# Ice-LogicBench.net
KiCad netlist of a schematic drawn in EAGLE
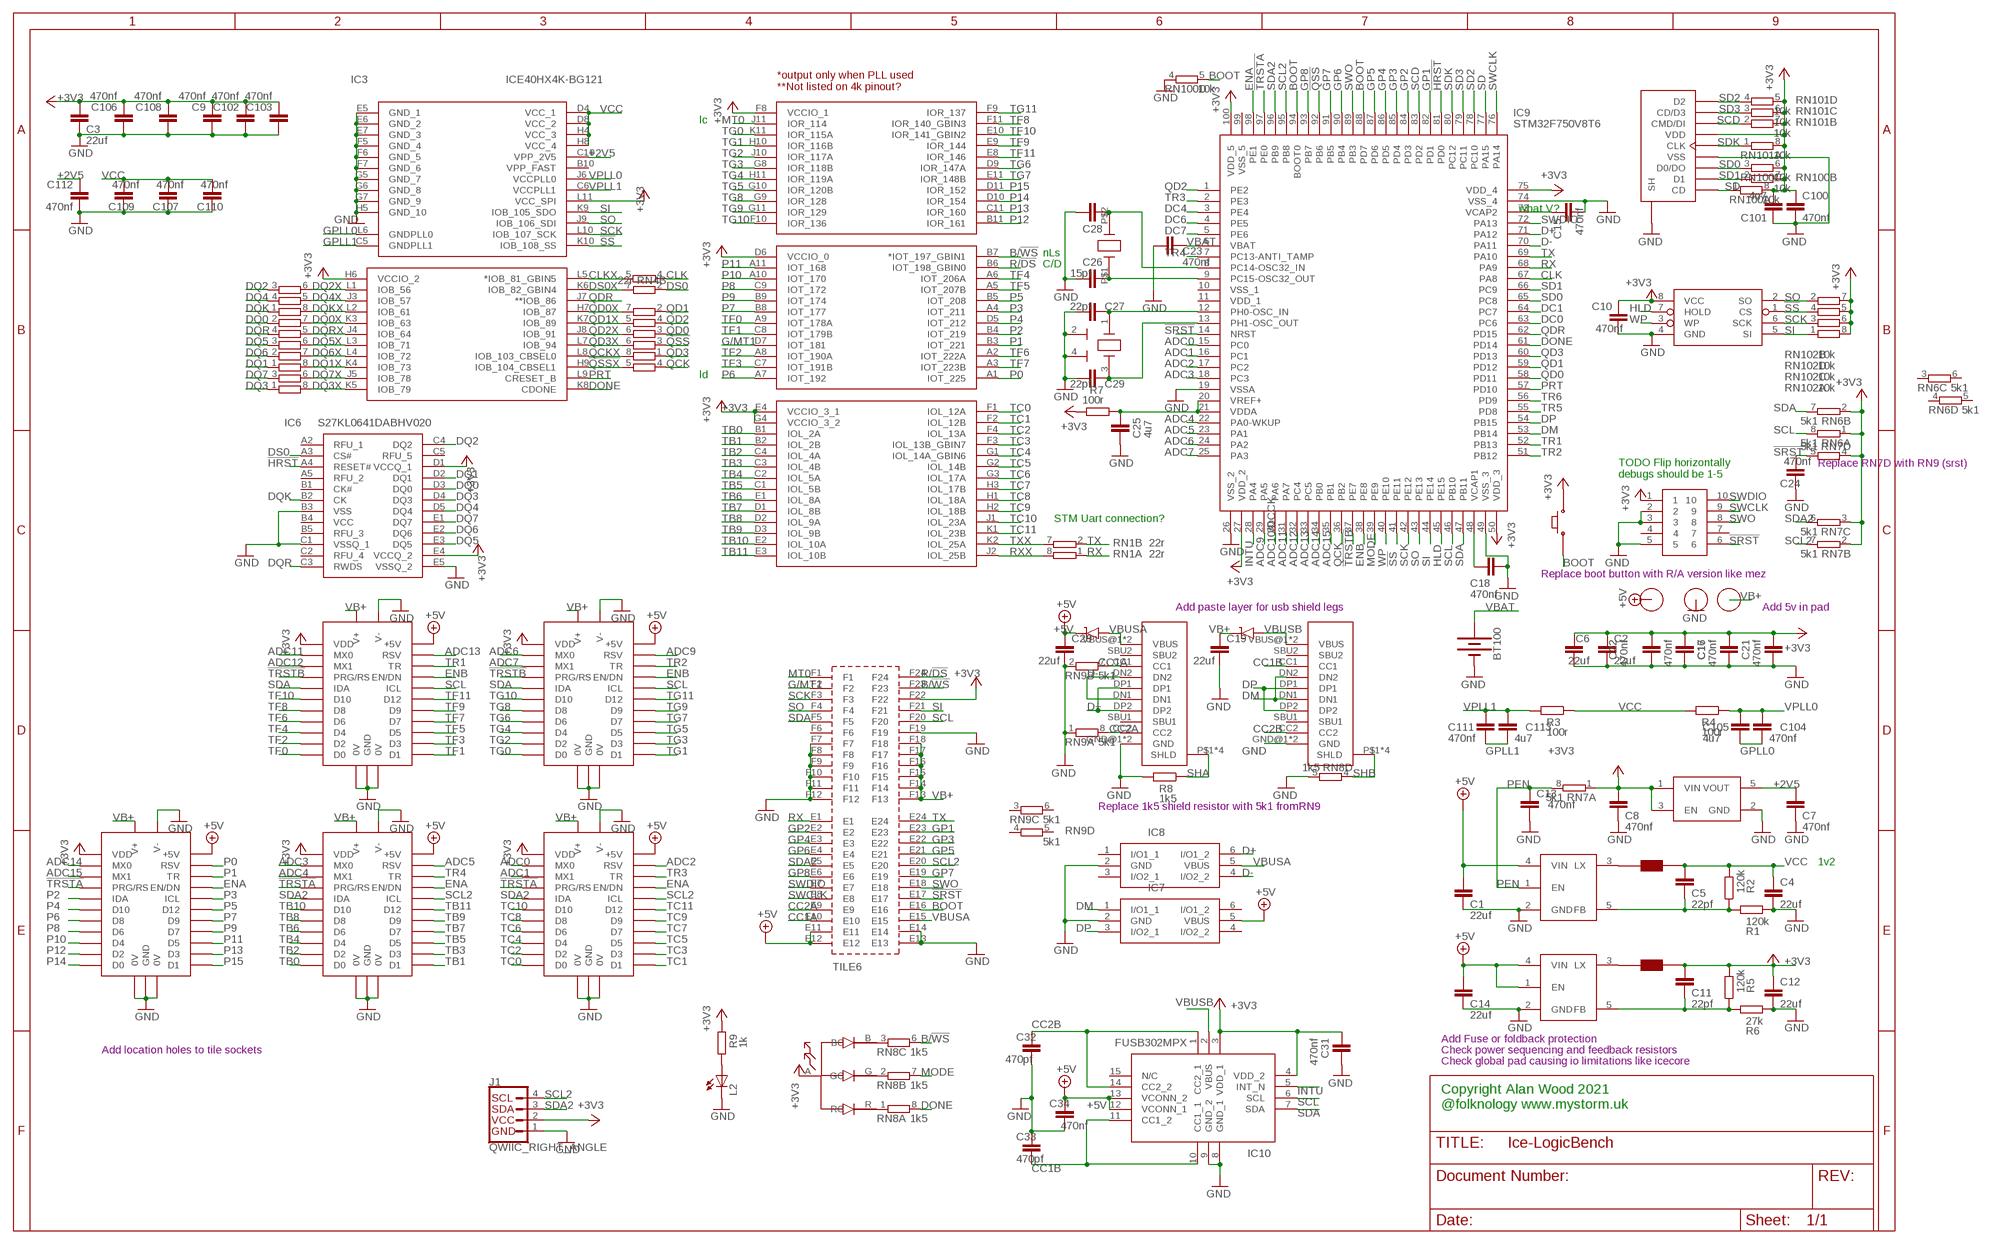
[diagram p0: schematic, sheet 1]

(export (version "E")
  (design (tool "Eeschema 10.0.6"))
  (components
    (comp (ref "B1")
      (value "PUSH_BUTTON")
      (footprint "eagle-import:3X4MM_BUTTON")
      (libsource (lib "eagle-import") (part "PUSH_BUTTON"))
    )
    (comp (ref "BT100")
      (value "BATTERY-20MM_SMD")
      (footprint "eagle-import:BATTCON_20MM")
      (libsource (lib "eagle-import") (part "BATTERY-20MM_SMD"))
    )
    (comp (ref "C1")
      (value "22uf")
      (footprint "eagle-import:C0603")
      (libsource (lib "eagle-import") (part "C-EUC0603"))
    )
    (comp (ref "C2")
      (value "22uf")
      (footprint "eagle-import:C0603")
      (libsource (lib "eagle-import") (part "C-EUC0603"))
    )
    (comp (ref "C3")
      (value "22uf")
      (footprint "eagle-import:C0603")
      (libsource (lib "eagle-import") (part "C-EUC0603"))
    )
    (comp (ref "C4")
      (value "22uf")
      (footprint "eagle-import:C0603")
      (libsource (lib "eagle-import") (part "C-EUC0603"))
    )
    (comp (ref "C5")
      (value "22pf")
      (footprint "eagle-import:C0402")
      (libsource (lib "eagle-import") (part "C-EUC0402"))
    )
    (comp (ref "C6")
      (value "22uf")
      (footprint "eagle-import:C0603")
      (libsource (lib "eagle-import") (part "C-EUC0603"))
    )
    (comp (ref "C7")
      (value "470nf")
      (footprint "eagle-import:C0402")
      (libsource (lib "eagle-import") (part "C-EUC0402"))
    )
    (comp (ref "C8")
      (value "470nf")
      (footprint "eagle-import:C0402")
      (libsource (lib "eagle-import") (part "C-EUC0402"))
    )
    (comp (ref "C9")
      (value "470nf")
      (footprint "eagle-import:C0402")
      (libsource (lib "eagle-import") (part "C-EUC0402"))
    )
    (comp (ref "C10")
      (value "470nf")
      (footprint "eagle-import:C0402")
      (libsource (lib "eagle-import") (part "C-EUC0402"))
    )
    (comp (ref "C11")
      (value "22pf")
      (footprint "eagle-import:C0402")
      (libsource (lib "eagle-import") (part "C-EUC0402"))
    )
    (comp (ref "C12")
      (value "22uf")
      (footprint "eagle-import:C0603")
      (libsource (lib "eagle-import") (part "C-EUC0603"))
    )
    (comp (ref "C13")
      (value "470nf")
      (footprint "eagle-import:C0402")
      (libsource (lib "eagle-import") (part "C-EUC0402"))
    )
    (comp (ref "C14")
      (value "22uf")
      (footprint "eagle-import:C0603")
      (libsource (lib "eagle-import") (part "C-EUC0603"))
    )
    (comp (ref "C15")
      (value "470nf")
      (footprint "eagle-import:C0402")
      (libsource (lib "eagle-import") (part "C-EUC0402"))
    )
    (comp (ref "C16")
      (value "470nf")
      (footprint "eagle-import:C0402")
      (libsource (lib "eagle-import") (part "C-EUC0402"))
    )
    (comp (ref "C17")
      (value "470nf")
      (footprint "eagle-import:C0402")
      (libsource (lib "eagle-import") (part "C-EUC0402"))
    )
    (comp (ref "C18")
      (value "470nf")
      (footprint "eagle-import:C0402")
      (libsource (lib "eagle-import") (part "C-EUC0402"))
    )
    (comp (ref "C19")
      (value "22uf")
      (footprint "eagle-import:C0603")
      (libsource (lib "eagle-import") (part "C-EUC0603"))
    )
    (comp (ref "C20")
      (value "22uf")
      (footprint "eagle-import:C0603")
      (libsource (lib "eagle-import") (part "C-EUC0603"))
    )
    (comp (ref "C21")
      (value "470nf")
      (footprint "eagle-import:C0402")
      (libsource (lib "eagle-import") (part "C-EUC0402"))
    )
    (comp (ref "C22")
      (value "470nf")
      (footprint "eagle-import:C0402")
      (libsource (lib "eagle-import") (part "C-EUC0402"))
    )
    (comp (ref "C23")
      (value "470nf")
      (footprint "eagle-import:C0402")
      (libsource (lib "eagle-import") (part "C-EUC0402"))
    )
    (comp (ref "C24")
      (value "470nf")
      (footprint "eagle-import:C0402")
      (libsource (lib "eagle-import") (part "C-EUC0402"))
    )
    (comp (ref "C25")
      (value "4u7")
      (footprint "eagle-import:C0402")
      (libsource (lib "eagle-import") (part "C-EUC0402"))
    )
    (comp (ref "C26")
      (value "15pf")
      (footprint "eagle-import:C0402")
      (libsource (lib "eagle-import") (part "C-EUC0402"))
    )
    (comp (ref "C27")
      (value "22pf")
      (footprint "eagle-import:C0402")
      (libsource (lib "eagle-import") (part "C-EUC0402"))
    )
    (comp (ref "C28")
      (value "15pf")
      (footprint "eagle-import:C0402")
      (libsource (lib "eagle-import") (part "C-EUC0402"))
    )
    (comp (ref "C29")
      (value "22pf")
      (footprint "eagle-import:C0402")
      (libsource (lib "eagle-import") (part "C-EUC0402"))
    )
    (comp (ref "C31")
      (value "470nf")
      (footprint "eagle-import:C0402")
      (libsource (lib "eagle-import") (part "C-EUC0402"))
    )
    (comp (ref "C32")
      (value "470pf")
      (footprint "eagle-import:C0402")
      (libsource (lib "eagle-import") (part "C-EUC0402"))
    )
    (comp (ref "C33")
      (value "470pf")
      (footprint "eagle-import:C0402")
      (libsource (lib "eagle-import") (part "C-EUC0402"))
    )
    (comp (ref "C34")
      (value "470nf")
      (footprint "eagle-import:C0402")
      (libsource (lib "eagle-import") (part "C-EUC0402"))
    )
    (comp (ref "C100")
      (value "470nf")
      (footprint "eagle-import:C0402")
      (libsource (lib "eagle-import") (part "C-EUC0402"))
    )
    (comp (ref "C101")
      (value "4u7")
      (footprint "eagle-import:C0402")
      (libsource (lib "eagle-import") (part "C-EUC0402"))
    )
    (comp (ref "C102")
      (value "470nf")
      (footprint "eagle-import:C0402")
      (libsource (lib "eagle-import") (part "C-EUC0402"))
    )
    (comp (ref "C103")
      (value "470nf")
      (footprint "eagle-import:C0402")
      (libsource (lib "eagle-import") (part "C-EUC0402"))
    )
    (comp (ref "C104")
      (value "470nf")
      (footprint "eagle-import:C0402")
      (libsource (lib "eagle-import") (part "C-EUC0402"))
    )
    (comp (ref "C105")
      (value "4u7")
      (footprint "eagle-import:C0402")
      (libsource (lib "eagle-import") (part "C-EUC0402"))
    )
    (comp (ref "C106")
      (value "470nf")
      (footprint "eagle-import:C0402")
      (libsource (lib "eagle-import") (part "C-EUC0402"))
    )
    (comp (ref "C107")
      (value "470nf")
      (footprint "eagle-import:C0402")
      (libsource (lib "eagle-import") (part "C-EUC0402"))
    )
    (comp (ref "C108")
      (value "470nf")
      (footprint "eagle-import:C0402")
      (libsource (lib "eagle-import") (part "C-EUC0402"))
    )
    (comp (ref "C109")
      (value "470nf")
      (footprint "eagle-import:C0402")
      (libsource (lib "eagle-import") (part "C-EUC0402"))
    )
    (comp (ref "C110")
      (value "470nf")
      (footprint "eagle-import:C0402")
      (libsource (lib "eagle-import") (part "C-EUC0402"))
    )
    (comp (ref "C111")
      (value "470nf")
      (footprint "eagle-import:C0402")
      (libsource (lib "eagle-import") (part "C-EUC0402"))
    )
    (comp (ref "C112")
      (value "470nf")
      (footprint "eagle-import:C0402")
      (libsource (lib "eagle-import") (part "C-EUC0402"))
    )
    (comp (ref "C113")
      (value "4u7")
      (footprint "eagle-import:C0402")
      (libsource (lib "eagle-import") (part "C-EUC0402"))
    )
    (comp (ref "CN1")
      (value "USB-C-16")
      (footprint "eagle-import:USB-C")
      (libsource (lib "eagle-import") (part "USB-C-16"))
    )
    (comp (ref "CN2")
      (value "USB-C-16")
      (footprint "eagle-import:USB-C")
      (libsource (lib "eagle-import") (part "USB-C-16"))
    )
    (comp (ref "CN3")
      (value "2X5-HEADER")
      (footprint "eagle-import:1.27-2X5-HEADER")
      (libsource (lib "eagle-import") (part "2X5-HEADER"))
    )
    (comp (ref "H1")
      (value "HOLE2.5MM-LARGE")
      (footprint "eagle-import:2M5-LARGE")
      (libsource (lib "eagle-import") (part "HOLE2.5MM-LARGE"))
    )
    (comp (ref "H3")
      (value "HOLE2.5MM-LARGE")
      (footprint "eagle-import:2M5-LARGE")
      (libsource (lib "eagle-import") (part "HOLE2.5MM-LARGE"))
    )
    (comp (ref "H4")
      (value "HOLE2.5MM-LARGE")
      (footprint "eagle-import:2M5-LARGE")
      (libsource (lib "eagle-import") (part "HOLE2.5MM-LARGE"))
    )
    (comp (ref "I1")
      (value "NRS4018")
      (footprint "eagle-import:NRC4018")
      (libsource (lib "eagle-import") (part "NRS4018"))
    )
    (comp (ref "I2")
      (value "NRS4018")
      (footprint "eagle-import:NRC4018")
      (libsource (lib "eagle-import") (part "NRS4018"))
    )
    (comp (ref "IC1")
      (value "AP3429/A")
      (footprint "eagle-import:TSOP-5_SOT23-5")
      (libsource (lib "eagle-import") (part "AP3429/A"))
    )
    (comp (ref "IC2")
      (value "NCP114")
      (footprint "eagle-import:TSOP-5_SOT23-5")
      (libsource (lib "eagle-import") (part "NCP114"))
    )
    (comp (ref "IC3")
      (value "ICE40HX4K-BG121")
      (footprint "eagle-import:BGA121C80P11X11_900X900X110")
      (fields (field (name "MOUSER_PART_NUMBER") "842-ICE40HX4K-BG121"))
      (libsource (lib "eagle-import") (part "ICE40HX4K-BG121"))
    )
    (comp (ref "IC4")
      (value "AT25SDF041A")
      (footprint "eagle-import:SOIC-8-NARROW")
      (libsource (lib "eagle-import") (part "AT25SDF041A"))
    )
    (comp (ref "IC5")
      (value "AP3429/A")
      (footprint "eagle-import:TSOP-5_SOT23-5")
      (libsource (lib "eagle-import") (part "AP3429/A"))
    )
    (comp (ref "IC6")
      (value "S27KL0641DABHV020")
      (footprint "eagle-import:BGA24C100P5X5_600X800X100")
      (fields (field (name "MOUSER_PART_NUMBER") "727-S27KL0641DABHV02"))
      (libsource (lib "eagle-import") (part "S27KL0641DABHV020"))
    )
    (comp (ref "IC7")
      (value "USBLC6-2SC6")
      (footprint "eagle-import:SOT95P280X145-6N")
      (fields (field (name "MOUSER_PART_NUMBER") "511-USBLC6-2SC6"))
      (libsource (lib "eagle-import") (part "USBLC6-2SC6"))
    )
    (comp (ref "IC8")
      (value "USBLC6-2SC6")
      (footprint "eagle-import:SOT95P280X145-6N")
      (fields (field (name "MOUSER_PART_NUMBER") "511-USBLC6-2SC6"))
      (libsource (lib "eagle-import") (part "USBLC6-2SC6"))
    )
    (comp (ref "IC9")
      (value "STM32F750V8T6")
      (footprint "eagle-import:QFP50P1600X1600X160-100N")
      (fields (field (name "MOUSER_PART_NUMBER") "511-STM32F750V8T6"))
      (libsource (lib "eagle-import") (part "STM32F750V8T6"))
    )
    (comp (ref "IC10")
      (value "FUSB302MPX")
      (footprint "eagle-import:QFN50P250X250X80-15N")
      (fields (field (name "MOUSER_PART_NUMBER") "512-FUSB302MPX"))
      (libsource (lib "eagle-import") (part "FUSB302MPX"))
    )
    (comp (ref "J1")
      (value "QWIIC_RIGHT_ANGLE")
      (footprint "eagle-import:JST04_1MM_RA")
      (libsource (lib "eagle-import") (part "QWIIC_CONNECTORJS-1MM"))
    )
    (comp (ref "L1")
      (value "RGB_LED")
      (footprint "eagle-import:RGB_LED_IMM")
      (libsource (lib "eagle-import") (part "RGB_LED"))
    )
    (comp (ref "L2")
      (value "LEDCHIPLED_1206")
      (footprint "eagle-import:CHIPLED_1206")
      (libsource (lib "eagle-import") (part "LEDCHIPLED_1206"))
    )
    (comp (ref "R1")
      (value "120k")
      (footprint "eagle-import:R0402")
      (libsource (lib "eagle-import") (part "R-EU_R0402"))
    )
    (comp (ref "R2")
      (value "120k")
      (footprint "eagle-import:R0402")
      (libsource (lib "eagle-import") (part "R-EU_R0402"))
    )
    (comp (ref "R3")
      (value "100r")
      (footprint "eagle-import:R0402")
      (libsource (lib "eagle-import") (part "R-EU_R0402"))
    )
    (comp (ref "R4")
      (value "100r")
      (footprint "eagle-import:R0402")
      (libsource (lib "eagle-import") (part "R-EU_R0402"))
    )
    (comp (ref "R5")
      (value "120k")
      (footprint "eagle-import:R0402")
      (libsource (lib "eagle-import") (part "R-EU_R0402"))
    )
    (comp (ref "R6")
      (value "27k")
      (footprint "eagle-import:R0402")
      (libsource (lib "eagle-import") (part "R-EU_R0402"))
    )
    (comp (ref "R7")
      (value "100r")
      (footprint "eagle-import:R0402")
      (libsource (lib "eagle-import") (part "R-EU_R0402"))
    )
    (comp (ref "R8")
      (value "1k5")
      (footprint "eagle-import:R0402")
      (libsource (lib "eagle-import") (part "R-EU_R0402"))
    )
    (comp (ref "R9")
      (value "1k")
      (footprint "eagle-import:R0402")
      (libsource (lib "eagle-import") (part "R-EU_R0402"))
    )
    (comp (ref "RN1")
      (value "22r")
      (footprint "eagle-import:EXB38V")
      (libsource (lib "eagle-import") (part "4R-NEXB38V"))
    )
    (comp (ref "RN2")
      (value "22r")
      (footprint "eagle-import:EXB38V")
      (libsource (lib "eagle-import") (part "4R-NEXB38V"))
    )
    (comp (ref "RN3")
      (value "22r")
      (footprint "eagle-import:EXB38V")
      (libsource (lib "eagle-import") (part "4R-NEXB38V"))
    )
    (comp (ref "RN4")
      (value "22r")
      (footprint "eagle-import:EXB38V")
      (libsource (lib "eagle-import") (part "4R-NEXB38V"))
    )
    (comp (ref "RN5")
      (value "22r")
      (footprint "eagle-import:EXB38V")
      (libsource (lib "eagle-import") (part "4R-NEXB38V"))
    )
    (comp (ref "RN6")
      (value "5k1")
      (footprint "eagle-import:EXB38V")
      (libsource (lib "eagle-import") (part "4R-NEXB38V"))
    )
    (comp (ref "RN7")
      (value "5k1")
      (footprint "eagle-import:EXB38V")
      (libsource (lib "eagle-import") (part "4R-NEXB38V"))
    )
    (comp (ref "RN8")
      (value "1k5")
      (footprint "eagle-import:EXB38V")
      (libsource (lib "eagle-import") (part "4R-NEXB38V"))
    )
    (comp (ref "RN9")
      (value "5k1")
      (footprint "eagle-import:EXB38V")
      (libsource (lib "eagle-import") (part "4R-NEXB38V"))
    )
    (comp (ref "RN100")
      (value "10k")
      (footprint "eagle-import:EXB38V")
      (libsource (lib "eagle-import") (part "4R-NEXB38V"))
    )
    (comp (ref "RN101")
      (value "10k")
      (footprint "eagle-import:EXB38V")
      (libsource (lib "eagle-import") (part "4R-NEXB38V"))
    )
    (comp (ref "RN102")
      (value "10k")
      (footprint "eagle-import:EXB38V")
      (libsource (lib "eagle-import") (part "4R-NEXB38V"))
    )
    (comp (ref "SD100")
      (value "TF-15X15")
      (footprint "eagle-import:SDCARD")
      (libsource (lib "eagle-import") (part "TF-15X15"))
    )
    (comp (ref "TILE1")
      (value "UTILE_LPCARRIER_SMD_MALE_1.27")
      (footprint "eagle-import:UTILE_LP")
      (libsource (lib "eagle-import") (part "UTILE_LPCARRIER_SMD_MALE_1.27"))
    )
    (comp (ref "TILE2")
      (value "UTILE_LPCARRIER_SMD_MALE_1.27")
      (footprint "eagle-import:UTILE_LP")
      (libsource (lib "eagle-import") (part "UTILE_LPCARRIER_SMD_MALE_1.27"))
    )
    (comp (ref "TILE3")
      (value "UTILE_LPCARRIER_SMD_MALE_1.27")
      (footprint "eagle-import:UTILE_LP")
      (libsource (lib "eagle-import") (part "UTILE_LPCARRIER_SMD_MALE_1.27"))
    )
    (comp (ref "TILE4")
      (value "UTILE_LPCARRIER_SMD_MALE_1.27")
      (footprint "eagle-import:UTILE_LP")
      (libsource (lib "eagle-import") (part "UTILE_LPCARRIER_SMD_MALE_1.27"))
    )
    (comp (ref "TILE5")
      (value "UTILE_LPCARRIER_SMD_MALE_1.27")
      (footprint "eagle-import:UTILE_LP")
      (libsource (lib "eagle-import") (part "UTILE_LPCARRIER_SMD_MALE_1.27"))
    )
    (comp (ref "TILE6")
      (value "HYPER-TILECARRIER")
      (footprint "eagle-import:HYPER-TILE")
      (libsource (lib "eagle-import") (part "HYPER-TILECARRIER"))
    )
    (comp (ref "U$1")
      (value "SS54")
      (footprint "eagle-import:SMA-NARROW")
      (libsource (lib "eagle-import") (part "SS54"))
    )
    (comp (ref "U$2")
      (value "SS54")
      (footprint "eagle-import:SMA-NARROW")
      (libsource (lib "eagle-import") (part "SS54"))
    )
    (comp (ref "Y1")
      (value "12MZ")
      (footprint "eagle-import:CRYSTAL-3.2X2.5")
      (libsource (lib "eagle-import") (part "7M-25"))
    )
    (comp (ref "Y2")
      (value "FC-135")
      (footprint "eagle-import:FC135")
      (libsource (lib "eagle-import") (part "FC-135"))
    )
  )
  (nets
    (net (code "1") (name "+3V3") (class "Default")
      (node (ref "B1") (pin "P$1") (pinfunction "P$1_P$1") (pintype "passive"))
      (node (ref "C10") (pin "1") (pinfunction "1_1") (pintype "passive"))
      (node (ref "C100") (pin "1") (pinfunction "1_1") (pintype "passive"))
      (node (ref "C101") (pin "2") (pinfunction "2_2") (pintype "passive"))
      (node (ref "C102") (pin "1") (pinfunction "1_1") (pintype "passive"))
      (node (ref "C103") (pin "1") (pinfunction "1_1") (pintype "passive"))
      (node (ref "C106") (pin "1") (pinfunction "1_1") (pintype "passive"))
      (node (ref "C108") (pin "1") (pinfunction "1_1") (pintype "passive"))
      (node (ref "C11") (pin "2") (pinfunction "2_2") (pintype "passive"))
      (node (ref "C12") (pin "1") (pinfunction "1_1") (pintype "passive"))
      (node (ref "C16") (pin "2") (pinfunction "2_2") (pintype "passive"))
      (node (ref "C17") (pin "2") (pinfunction "2_2") (pintype "passive"))
      (node (ref "C2") (pin "1") (pinfunction "1_1") (pintype "passive"))
      (node (ref "C21") (pin "2") (pinfunction "2_2") (pintype "passive"))
      (node (ref "C22") (pin "2") (pinfunction "2_2") (pintype "passive"))
      (node (ref "C3") (pin "2") (pinfunction "2_2") (pintype "passive"))
      (node (ref "C31") (pin "2") (pinfunction "2_2") (pintype "passive"))
      (node (ref "C6") (pin "2") (pinfunction "2_2") (pintype "passive"))
      (node (ref "C8") (pin "2") (pinfunction "2_2") (pintype "passive"))
      (node (ref "C9") (pin "1") (pinfunction "1_1") (pintype "passive"))
      (node (ref "CN3") (pin "1") (pinfunction "1_1") (pintype "bidirectional"))
      (node (ref "I2") (pin "P$2") (pinfunction "P$2_P$2") (pintype "passive"))
      (node (ref "IC10") (pin "3") (pinfunction "VDD_1_3") (pintype "bidirectional"))
      (node (ref "IC10") (pin "4") (pinfunction "VDD_2_4") (pintype "bidirectional"))
      (node (ref "IC2") (pin "1") (pinfunction "VIN_1") (pintype "power_in"))
      (node (ref "IC2") (pin "3") (pinfunction "EN_3") (pintype "input"))
      (node (ref "IC3") (pin "D6") (pinfunction "VCCIO_0_D6") (pintype "bidirectional"))
      (node (ref "IC3") (pin "E4") (pinfunction "VCCIO_3_1_E4") (pintype "bidirectional"))
      (node (ref "IC3") (pin "F8") (pinfunction "VCCIO_1_F8") (pintype "bidirectional"))
      (node (ref "IC3") (pin "G4") (pinfunction "VCCIO_3_2_G4") (pintype "bidirectional"))
      (node (ref "IC3") (pin "H6") (pinfunction "VCCIO_2_H6") (pintype "bidirectional"))
      (node (ref "IC3") (pin "L11") (pinfunction "VCC_SPI_L11") (pintype "bidirectional"))
      (node (ref "IC4") (pin "8") (pinfunction "VCC_8") (pintype "power_in"))
      (node (ref "IC6") (pin "D1") (pinfunction "VCCQ_1_D1") (pintype "bidirectional"))
      (node (ref "IC6") (pin "E4") (pinfunction "VCCQ_2_E4") (pintype "bidirectional"))
      (node (ref "IC9") (pin "100") (pinfunction "VDD_5_100") (pintype "bidirectional"))
      (node (ref "IC9") (pin "27") (pinfunction "VDD_2_27") (pintype "bidirectional"))
      (node (ref "IC9") (pin "50") (pinfunction "VDD_3_50") (pintype "bidirectional"))
      (node (ref "IC9") (pin "75") (pinfunction "VDD_4_75") (pintype "bidirectional"))
      (node (ref "J1") (pin "2") (pinfunction "2_2") (pintype "power_in"))
      (node (ref "L1") (pin "A") (pinfunction "ANODE_A") (pintype "bidirectional"))
      (node (ref "R5") (pin "2") (pinfunction "2_2") (pintype "passive"))
      (node (ref "R7") (pin "2") (pinfunction "2_2") (pintype "passive"))
      (node (ref "R9") (pin "1") (pinfunction "1_1") (pintype "passive"))
      (node (ref "RN100") (pin "6") (pinfunction "2_6") (pintype "passive"))
      (node (ref "RN100") (pin "7") (pinfunction "2_7") (pintype "passive"))
      (node (ref "RN100") (pin "8") (pinfunction "2_8") (pintype "passive"))
      (node (ref "RN101") (pin "5") (pinfunction "2_5") (pintype "passive"))
      (node (ref "RN101") (pin "6") (pinfunction "2_6") (pintype "passive"))
      (node (ref "RN101") (pin "7") (pinfunction "2_7") (pintype "passive"))
      (node (ref "RN101") (pin "8") (pinfunction "2_8") (pintype "passive"))
      (node (ref "RN102") (pin "5") (pinfunction "2_5") (pintype "passive"))
      (node (ref "RN102") (pin "6") (pinfunction "2_6") (pintype "passive"))
      (node (ref "RN102") (pin "7") (pinfunction "2_7") (pintype "passive"))
      (node (ref "RN102") (pin "8") (pinfunction "2_8") (pintype "passive"))
      (node (ref "RN6") (pin "1") (pinfunction "1_1") (pintype "passive"))
      (node (ref "RN6") (pin "2") (pinfunction "1_2") (pintype "passive"))
      (node (ref "RN7") (pin "1") (pinfunction "1_1") (pintype "passive"))
      (node (ref "RN7") (pin "2") (pinfunction "1_2") (pintype "passive"))
      (node (ref "RN7") (pin "3") (pinfunction "1_3") (pintype "passive"))
      (node (ref "RN7") (pin "4") (pinfunction "1_4") (pintype "passive"))
      (node (ref "SD100") (pin "P$6") (pinfunction "VDD_P$6") (pintype "power_in"))
      (node (ref "TILE1") (pin "P$18") (pinfunction "VDD_P$18") (pintype "power_in"))
      (node (ref "TILE2") (pin "P$18") (pinfunction "VDD_P$18") (pintype "power_in"))
      (node (ref "TILE3") (pin "P$18") (pinfunction "VDD_P$18") (pintype "power_in"))
      (node (ref "TILE4") (pin "P$18") (pinfunction "VDD_P$18") (pintype "power_in"))
      (node (ref "TILE5") (pin "P$18") (pinfunction "VDD_P$18") (pintype "power_in"))
      (node (ref "TILE6") (pin "F22") (pinfunction "F22_F22") (pintype "bidirectional"))
    )
    (net (code "2") (name "+5V") (class "Default")
      (node (ref "C1") (pin "2") (pinfunction "2_2") (pintype "passive"))
      (node (ref "C14") (pin "2") (pinfunction "2_2") (pintype "passive"))
      (node (ref "C20") (pin "1") (pinfunction "1_1") (pintype "passive"))
      (node (ref "C34") (pin "2") (pinfunction "2_2") (pintype "passive"))
      (node (ref "H1") (pin "P$1") (pinfunction "P_P$1") (pintype "bidirectional"))
      (node (ref "IC1") (pin "4") (pinfunction "VIN_4") (pintype "power_in"))
      (node (ref "IC10") (pin "12") (pinfunction "VCONN_1_12") (pintype "bidirectional"))
      (node (ref "IC10") (pin "13") (pinfunction "VCONN_2_13") (pintype "bidirectional"))
      (node (ref "IC5") (pin "1") (pinfunction "EN_1") (pintype "input"))
      (node (ref "IC5") (pin "4") (pinfunction "VIN_4") (pintype "power_in"))
      (node (ref "IC7") (pin "5") (pinfunction "VBUS_5") (pintype "bidirectional"))
      (node (ref "TILE1") (pin "P$43") (pinfunction "+5V_P$43") (pintype "power_in"))
      (node (ref "TILE2") (pin "P$43") (pinfunction "+5V_P$43") (pintype "power_in"))
      (node (ref "TILE3") (pin "P$43") (pinfunction "+5V_P$43") (pintype "power_in"))
      (node (ref "TILE4") (pin "P$43") (pinfunction "+5V_P$43") (pintype "power_in"))
      (node (ref "TILE5") (pin "P$43") (pinfunction "+5V_P$43") (pintype "power_in"))
      (node (ref "TILE6") (pin "E11") (pinfunction "E11_E11") (pintype "bidirectional"))
      (node (ref "TILE6") (pin "E12") (pinfunction "E12_E12") (pintype "bidirectional"))
      (node (ref "U$2") (pin "C") (pinfunction "CATHODE_C") (pintype "passive"))
    )
    (net (code "3") (name "/+2V5") (class "Default")
      (node (ref "C112") (pin "1") (pinfunction "1_1") (pintype "passive"))
      (node (ref "C7") (pin "2") (pinfunction "2_2") (pintype "passive"))
      (node (ref "IC2") (pin "5") (pinfunction "VOUT_5") (pintype "power_in"))
      (node (ref "IC3") (pin "C10") (pinfunction "VPP_2V5_C10") (pintype "bidirectional"))
    )
    (net (code "4") (name "/ADC0") (class "Default")
      (node (ref "IC9") (pin "15") (pinfunction "PC0_15") (pintype "bidirectional"))
      (node (ref "TILE4") (pin "P$17") (pinfunction "MX0_P$17") (pintype "bidirectional"))
    )
    (net (code "5") (name "/ADC1") (class "Default")
      (node (ref "IC9") (pin "16") (pinfunction "PC1_16") (pintype "bidirectional"))
      (node (ref "TILE4") (pin "P$16") (pinfunction "MX1_P$16") (pintype "bidirectional"))
    )
    (net (code "6") (name "/ADC2") (class "Default")
      (node (ref "IC9") (pin "17") (pinfunction "PC2_17") (pintype "bidirectional"))
      (node (ref "TILE4") (pin "P$42") (pinfunction "RSV_P$42") (pintype "bidirectional"))
    )
    (net (code "7") (name "/ADC3") (class "Default")
      (node (ref "IC9") (pin "18") (pinfunction "PC3_18") (pintype "bidirectional"))
      (node (ref "TILE1") (pin "P$17") (pinfunction "MX0_P$17") (pintype "bidirectional"))
    )
    (net (code "8") (name "/ADC4") (class "Default")
      (node (ref "IC9") (pin "22") (pinfunction "PA0-WKUP_22") (pintype "bidirectional"))
      (node (ref "TILE1") (pin "P$16") (pinfunction "MX1_P$16") (pintype "bidirectional"))
    )
    (net (code "9") (name "/ADC5") (class "Default")
      (node (ref "IC9") (pin "23") (pinfunction "PA1_23") (pintype "bidirectional"))
      (node (ref "TILE1") (pin "P$42") (pinfunction "RSV_P$42") (pintype "bidirectional"))
    )
    (net (code "10") (name "/ADC6") (class "Default")
      (node (ref "IC9") (pin "24") (pinfunction "PA2_24") (pintype "bidirectional"))
      (node (ref "TILE5") (pin "P$17") (pinfunction "MX0_P$17") (pintype "bidirectional"))
    )
    (net (code "11") (name "/ADC7") (class "Default")
      (node (ref "IC9") (pin "25") (pinfunction "PA3_25") (pintype "bidirectional"))
      (node (ref "TILE5") (pin "P$16") (pinfunction "MX1_P$16") (pintype "bidirectional"))
    )
    (net (code "12") (name "/ADC9") (class "Default")
      (node (ref "IC9") (pin "29") (pinfunction "PA5_29") (pintype "bidirectional"))
      (node (ref "TILE5") (pin "P$42") (pinfunction "RSV_P$42") (pintype "bidirectional"))
    )
    (net (code "13") (name "/ADC10{slash}DCCK") (class "Default")
      (node (ref "IC9") (pin "30") (pinfunction "PA6_30") (pintype "bidirectional"))
    )
    (net (code "14") (name "/ADC11") (class "Default")
      (node (ref "IC9") (pin "31") (pinfunction "PA7_31") (pintype "bidirectional"))
      (node (ref "TILE3") (pin "P$17") (pinfunction "MX0_P$17") (pintype "bidirectional"))
    )
    (net (code "15") (name "/ADC12") (class "Default")
      (node (ref "IC9") (pin "32") (pinfunction "PC4_32") (pintype "bidirectional"))
      (node (ref "TILE3") (pin "P$16") (pinfunction "MX1_P$16") (pintype "bidirectional"))
    )
    (net (code "16") (name "/ADC13") (class "Default")
      (node (ref "IC9") (pin "33") (pinfunction "PC5_33") (pintype "bidirectional"))
      (node (ref "TILE3") (pin "P$42") (pinfunction "RSV_P$42") (pintype "bidirectional"))
    )
    (net (code "17") (name "/ADC14") (class "Default")
      (node (ref "IC9") (pin "34") (pinfunction "PB0_34") (pintype "bidirectional"))
      (node (ref "TILE2") (pin "P$17") (pinfunction "MX0_P$17") (pintype "bidirectional"))
    )
    (net (code "18") (name "/ADC15") (class "Default")
      (node (ref "IC9") (pin "35") (pinfunction "PB1_35") (pintype "bidirectional"))
      (node (ref "TILE2") (pin "P$16") (pinfunction "MX1_P$16") (pintype "bidirectional"))
    )
    (net (code "19") (name "/BOOT") (class "Default")
      (node (ref "B1") (pin "P$2") (pinfunction "P$2_P$2") (pintype "passive"))
      (node (ref "IC9") (pin "88") (pinfunction "PD7_88") (pintype "bidirectional"))
      (node (ref "IC9") (pin "94") (pinfunction "BOOT0_94") (pintype "bidirectional"))
      (node (ref "RN100") (pin "5") (pinfunction "2_5") (pintype "passive"))
      (node (ref "TILE6") (pin "E16") (pinfunction "E16_E16") (pintype "bidirectional"))
    )
    (net (code "20") (name "/B{slash}~{WS}") (class "Default")
      (node (ref "IC3") (pin "B7") (pinfunction "*IOT_197_GBIN1_B7") (pintype "bidirectional"))
      (node (ref "RN8") (pin "6") (pinfunction "2_6") (pintype "passive"))
      (node (ref "TILE6") (pin "F23") (pinfunction "F23_F23") (pintype "bidirectional"))
    )
    (net (code "21") (name "/CC1A") (class "Default")
      (node (ref "CN1") (pin "CC1") (pinfunction "CC1_CC1") (pintype "bidirectional"))
      (node (ref "RN9") (pin "7") (pinfunction "2_7") (pintype "passive"))
      (node (ref "TILE6") (pin "E10") (pinfunction "E10_E10") (pintype "bidirectional"))
    )
    (net (code "22") (name "/CC1B") (class "Default")
      (node (ref "C33") (pin "1") (pinfunction "1_1") (pintype "passive"))
      (node (ref "CN2") (pin "CC1") (pinfunction "CC1_CC1") (pintype "bidirectional"))
      (node (ref "IC10") (pin "10") (pinfunction "CC1_1_10") (pintype "bidirectional"))
      (node (ref "IC10") (pin "11") (pinfunction "CC1_2_11") (pintype "bidirectional"))
    )
    (net (code "23") (name "/CC2A") (class "Default")
      (node (ref "CN1") (pin "CC2") (pinfunction "CC2_CC2") (pintype "bidirectional"))
      (node (ref "RN9") (pin "8") (pinfunction "2_8") (pintype "passive"))
      (node (ref "TILE6") (pin "E9") (pinfunction "E9_E9") (pintype "bidirectional"))
    )
    (net (code "24") (name "/CC2B") (class "Default")
      (node (ref "C32") (pin "2") (pinfunction "2_2") (pintype "passive"))
      (node (ref "CN2") (pin "CC2") (pinfunction "CC2_CC2") (pintype "bidirectional"))
      (node (ref "IC10") (pin "1") (pinfunction "CC2_1_1") (pintype "bidirectional"))
      (node (ref "IC10") (pin "14") (pinfunction "CC2_2_14") (pintype "bidirectional"))
    )
    (net (code "25") (name "/CLK") (class "Default")
      (node (ref "IC9") (pin "67") (pinfunction "PA8_67") (pintype "bidirectional"))
      (node (ref "RN3") (pin "4") (pinfunction "1_4") (pintype "passive"))
    )
    (net (code "26") (name "/CLKX") (class "Default")
      (node (ref "IC3") (pin "L5") (pinfunction "*IOB_81_GBIN5_L5") (pintype "bidirectional"))
      (node (ref "RN3") (pin "5") (pinfunction "2_5") (pintype "passive"))
    )
    (net (code "27") (name "/D+") (class "Default")
      (node (ref "CN1") (pin "DP1") (pinfunction "DP1_DP1") (pintype "bidirectional"))
      (node (ref "CN1") (pin "DP2") (pinfunction "DP2_DP2") (pintype "bidirectional"))
      (node (ref "IC8") (pin "6") (pinfunction "I/O1_2_6") (pintype "bidirectional"))
      (node (ref "IC9") (pin "71") (pinfunction "PA12_71") (pintype "bidirectional"))
    )
    (net (code "28") (name "/D-") (class "Default")
      (node (ref "CN1") (pin "DN1") (pinfunction "DN1_DN1") (pintype "bidirectional"))
      (node (ref "CN1") (pin "DN2") (pinfunction "DN2_DN2") (pintype "bidirectional"))
      (node (ref "IC8") (pin "4") (pinfunction "I/O2_2_4") (pintype "bidirectional"))
      (node (ref "IC9") (pin "70") (pinfunction "PA11_70") (pintype "bidirectional"))
    )
    (net (code "29") (name "/DC0") (class "Default")
      (node (ref "IC9") (pin "63") (pinfunction "PC6_63") (pintype "bidirectional"))
    )
    (net (code "30") (name "/DC1") (class "Default")
      (node (ref "IC9") (pin "64") (pinfunction "PC7_64") (pintype "bidirectional"))
    )
    (net (code "31") (name "/DC4") (class "Default")
      (node (ref "IC9") (pin "3") (pinfunction "PE4_3") (pintype "bidirectional"))
    )
    (net (code "32") (name "/DC6") (class "Default")
      (node (ref "IC9") (pin "4") (pinfunction "PE5_4") (pintype "bidirectional"))
    )
    (net (code "33") (name "/DC7") (class "Default")
      (node (ref "IC9") (pin "5") (pinfunction "PE6_5") (pintype "bidirectional"))
    )
    (net (code "34") (name "/DM") (class "Default")
      (node (ref "CN2") (pin "DN1") (pinfunction "DN1_DN1") (pintype "bidirectional"))
      (node (ref "CN2") (pin "DN2") (pinfunction "DN2_DN2") (pintype "bidirectional"))
      (node (ref "IC7") (pin "1") (pinfunction "I/O1_1_1") (pintype "bidirectional"))
      (node (ref "IC9") (pin "53") (pinfunction "PB14_53") (pintype "bidirectional"))
    )
    (net (code "35") (name "/DONE") (class "Default")
      (node (ref "IC3") (pin "K8") (pinfunction "CDONE_K8") (pintype "bidirectional"))
      (node (ref "IC9") (pin "61") (pinfunction "PD14_61") (pintype "bidirectional"))
      (node (ref "RN8") (pin "8") (pinfunction "2_8") (pintype "passive"))
    )
    (net (code "36") (name "/DP") (class "Default")
      (node (ref "CN2") (pin "DP1") (pinfunction "DP1_DP1") (pintype "bidirectional"))
      (node (ref "CN2") (pin "DP2") (pinfunction "DP2_DP2") (pintype "bidirectional"))
      (node (ref "IC7") (pin "3") (pinfunction "I/O2_1_3") (pintype "bidirectional"))
      (node (ref "IC9") (pin "54") (pinfunction "PB15_54") (pintype "bidirectional"))
    )
    (net (code "37") (name "/DQ0") (class "Default")
      (node (ref "IC6") (pin "D3") (pinfunction "DQ0_D3") (pintype "bidirectional"))
      (node (ref "RN2") (pin "2") (pinfunction "1_2") (pintype "passive"))
    )
    (net (code "38") (name "/DQ0X") (class "Default")
      (node (ref "IC3") (pin "K3") (pinfunction "IOB_63_K3") (pintype "bidirectional"))
      (node (ref "RN2") (pin "7") (pinfunction "2_7") (pintype "passive"))
    )
    (net (code "39") (name "/DQ1") (class "Default")
      (node (ref "IC6") (pin "D2") (pinfunction "DQ1_D2") (pintype "bidirectional"))
      (node (ref "RN3") (pin "1") (pinfunction "1_1") (pintype "passive"))
    )
    (net (code "40") (name "/DQ1X") (class "Default")
      (node (ref "IC3") (pin "K4") (pinfunction "IOB_73_K4") (pintype "bidirectional"))
      (node (ref "RN3") (pin "8") (pinfunction "2_8") (pintype "passive"))
    )
    (net (code "41") (name "/DQ2") (class "Default")
      (node (ref "IC6") (pin "C4") (pinfunction "DQ2_C4") (pintype "bidirectional"))
      (node (ref "RN1") (pin "3") (pinfunction "1_3") (pintype "passive"))
    )
    (net (code "42") (name "/DQ2X") (class "Default")
      (node (ref "IC3") (pin "L1") (pinfunction "IOB_56_L1") (pintype "bidirectional"))
      (node (ref "RN1") (pin "6") (pinfunction "2_6") (pintype "passive"))
    )
    (net (code "43") (name "/DQ3") (class "Default")
      (node (ref "IC6") (pin "D4") (pinfunction "DQ3_D4") (pintype "bidirectional"))
      (node (ref "RN4") (pin "1") (pinfunction "1_1") (pintype "passive"))
    )
    (net (code "44") (name "/DQ3X") (class "Default")
      (node (ref "IC3") (pin "K5") (pinfunction "IOB_79_K5") (pintype "bidirectional"))
      (node (ref "RN4") (pin "8") (pinfunction "2_8") (pintype "passive"))
    )
    (net (code "45") (name "/DQ4") (class "Default")
      (node (ref "IC6") (pin "D5") (pinfunction "DQ4_D5") (pintype "bidirectional"))
      (node (ref "RN1") (pin "4") (pinfunction "1_4") (pintype "passive"))
    )
    (net (code "46") (name "/DQ4X") (class "Default")
      (node (ref "IC3") (pin "J3") (pinfunction "IOB_57_J3") (pintype "bidirectional"))
      (node (ref "RN1") (pin "5") (pinfunction "2_5") (pintype "passive"))
    )
    (net (code "47") (name "/DQ5") (class "Default")
      (node (ref "IC6") (pin "E3") (pinfunction "DQ5_E3") (pintype "bidirectional"))
      (node (ref "RN2") (pin "3") (pinfunction "1_3") (pintype "passive"))
    )
    (net (code "48") (name "/DQ5X") (class "Default")
      (node (ref "IC3") (pin "L3") (pinfunction "IOB_71_L3") (pintype "bidirectional"))
      (node (ref "RN2") (pin "6") (pinfunction "2_6") (pintype "passive"))
    )
    (net (code "49") (name "/DQ6") (class "Default")
      (node (ref "IC6") (pin "E2") (pinfunction "DQ6_E2") (pintype "bidirectional"))
      (node (ref "RN3") (pin "2") (pinfunction "1_2") (pintype "passive"))
    )
    (net (code "50") (name "/DQ6X") (class "Default")
      (node (ref "IC3") (pin "L4") (pinfunction "IOB_72_L4") (pintype "bidirectional"))
      (node (ref "RN3") (pin "7") (pinfunction "2_7") (pintype "passive"))
    )
    (net (code "51") (name "/DQ7") (class "Default")
      (node (ref "IC6") (pin "E1") (pinfunction "DQ7_E1") (pintype "bidirectional"))
      (node (ref "RN3") (pin "3") (pinfunction "1_3") (pintype "passive"))
    )
    (net (code "52") (name "/DQ7X") (class "Default")
      (node (ref "IC3") (pin "J5") (pinfunction "IOB_78_J5") (pintype "bidirectional"))
      (node (ref "RN3") (pin "6") (pinfunction "2_6") (pintype "passive"))
    )
    (net (code "53") (name "/DQK") (class "Default")
      (node (ref "IC6") (pin "B2") (pinfunction "CK_B2") (pintype "bidirectional"))
      (node (ref "RN2") (pin "1") (pinfunction "1_1") (pintype "passive"))
    )
    (net (code "54") (name "/DQKX") (class "Default")
      (node (ref "IC3") (pin "L2") (pinfunction "IOB_61_L2") (pintype "bidirectional"))
      (node (ref "RN2") (pin "8") (pinfunction "2_8") (pintype "passive"))
    )
    (net (code "55") (name "/DQR") (class "Default")
      (node (ref "IC6") (pin "C3") (pinfunction "RWDS_C3") (pintype "bidirectional"))
      (node (ref "RN2") (pin "4") (pinfunction "1_4") (pintype "passive"))
    )
    (net (code "56") (name "/DQRX") (class "Default")
      (node (ref "IC3") (pin "J4") (pinfunction "IOB_64_J4") (pintype "bidirectional"))
      (node (ref "RN2") (pin "5") (pinfunction "2_5") (pintype "passive"))
    )
    (net (code "57") (name "/DS0") (class "Default")
      (node (ref "IC6") (pin "A3") (pinfunction "CS#_A3") (pintype "bidirectional"))
      (node (ref "RN4") (pin "2") (pinfunction "1_2") (pintype "passive"))
    )
    (net (code "58") (name "/DS0X") (class "Default")
      (node (ref "IC3") (pin "K6") (pinfunction "IOB_82_GBIN4_K6") (pintype "bidirectional"))
      (node (ref "RN4") (pin "7") (pinfunction "2_7") (pintype "passive"))
    )
    (net (code "59") (name "/ENA") (class "Default")
      (node (ref "IC9") (pin "98") (pinfunction "PE1_98") (pintype "bidirectional"))
      (node (ref "TILE1") (pin "P$40") (pinfunction "EN/DN_P$40") (pintype "open_collector"))
      (node (ref "TILE2") (pin "P$40") (pinfunction "EN/DN_P$40") (pintype "open_collector"))
      (node (ref "TILE4") (pin "P$40") (pinfunction "EN/DN_P$40") (pintype "open_collector"))
    )
    (net (code "60") (name "/ENB") (class "Default")
      (node (ref "IC9") (pin "38") (pinfunction "PE8_38") (pintype "bidirectional"))
      (node (ref "TILE3") (pin "P$40") (pinfunction "EN/DN_P$40") (pintype "open_collector"))
      (node (ref "TILE5") (pin "P$40") (pinfunction "EN/DN_P$40") (pintype "open_collector"))
    )
    (net (code "61") (name "/GP1") (class "Default")
      (node (ref "IC9") (pin "82") (pinfunction "PD1_82") (pintype "bidirectional"))
      (node (ref "TILE6") (pin "E23") (pinfunction "E23_E23") (pintype "bidirectional"))
    )
    (net (code "62") (name "/GP2") (class "Default")
      (node (ref "IC9") (pin "84") (pinfunction "PD3_84") (pintype "bidirectional"))
      (node (ref "TILE6") (pin "E2") (pinfunction "E2_E2") (pintype "bidirectional"))
    )
    (net (code "63") (name "/GP3") (class "Default")
      (node (ref "IC9") (pin "85") (pinfunction "PD4_85") (pintype "bidirectional"))
      (node (ref "TILE6") (pin "E22") (pinfunction "E22_E22") (pintype "bidirectional"))
    )
    (net (code "64") (name "/GP4") (class "Default")
      (node (ref "IC9") (pin "86") (pinfunction "PD5_86") (pintype "bidirectional"))
      (node (ref "TILE6") (pin "E3") (pinfunction "E3_E3") (pintype "bidirectional"))
    )
    (net (code "65") (name "/GP5") (class "Default")
      (node (ref "IC9") (pin "87") (pinfunction "PD6_87") (pintype "bidirectional"))
      (node (ref "TILE6") (pin "E21") (pinfunction "E21_E21") (pintype "bidirectional"))
    )
    (net (code "66") (name "/GP6") (class "Default")
      (node (ref "IC9") (pin "90") (pinfunction "PB4_90") (pintype "bidirectional"))
      (node (ref "TILE6") (pin "E4") (pinfunction "E4_E4") (pintype "bidirectional"))
    )
    (net (code "67") (name "/GP7") (class "Default")
      (node (ref "IC9") (pin "91") (pinfunction "PB5_91") (pintype "bidirectional"))
      (node (ref "TILE6") (pin "E19") (pinfunction "E19_E19") (pintype "bidirectional"))
    )
    (net (code "68") (name "/GP8") (class "Default")
      (node (ref "IC9") (pin "93") (pinfunction "PB7_93") (pintype "bidirectional"))
      (node (ref "TILE6") (pin "E6") (pinfunction "E6_E6") (pintype "bidirectional"))
    )
    (net (code "69") (name "/GPLL0") (class "Default")
      (node (ref "C104") (pin "1") (pinfunction "1_1") (pintype "passive"))
      (node (ref "C105") (pin "1") (pinfunction "1_1") (pintype "passive"))
      (node (ref "IC3") (pin "L6") (pinfunction "GNDPLL0_L6") (pintype "bidirectional"))
    )
    (net (code "70") (name "/GPLL1") (class "Default")
      (node (ref "C111") (pin "1") (pinfunction "1_1") (pintype "passive"))
      (node (ref "C113") (pin "1") (pinfunction "1_1") (pintype "passive"))
      (node (ref "IC3") (pin "C5") (pinfunction "GNDPLL1_C5") (pintype "bidirectional"))
    )
    (net (code "71") (name "/G{slash}MT1") (class "Default")
      (node (ref "IC3") (pin "D7") (pinfunction "IOT_181_D7") (pintype "bidirectional"))
      (node (ref "TILE6") (pin "F2") (pinfunction "F2_F2") (pintype "bidirectional"))
    )
    (net (code "72") (name "/HLD") (class "Default")
      (node (ref "IC4") (pin "7") (pinfunction "HOLD_7") (pintype "bidirectional"))
      (node (ref "IC9") (pin "45") (pinfunction "PE15_45") (pintype "bidirectional"))
    )
    (net (code "73") (name "/INTU") (class "Default")
      (node (ref "IC10") (pin "5") (pinfunction "INT_N_5") (pintype "bidirectional"))
      (node (ref "IC9") (pin "28") (pinfunction "PA4_28") (pintype "bidirectional"))
    )
    (net (code "74") (name "/MODE") (class "Default")
      (node (ref "IC9") (pin "39") (pinfunction "PE9_39") (pintype "bidirectional"))
      (node (ref "RN8") (pin "7") (pinfunction "2_7") (pintype "passive"))
    )
    (net (code "75") (name "/MT0") (class "Default")
      (node (ref "IC3") (pin "J11") (pinfunction "IOR_114_J11") (pintype "bidirectional"))
      (node (ref "TILE6") (pin "F1") (pinfunction "F1_F1") (pintype "bidirectional"))
    )
    (net (code "76") (name "/P0") (class "Default")
      (node (ref "IC3") (pin "A1") (pinfunction "IOT_225_A1") (pintype "bidirectional"))
      (node (ref "TILE2") (pin "P$42") (pinfunction "RSV_P$42") (pintype "bidirectional"))
    )
    (net (code "77") (name "/P1") (class "Default")
      (node (ref "IC3") (pin "B3") (pinfunction "IOT_221_B3") (pintype "bidirectional"))
      (node (ref "TILE2") (pin "P$41") (pinfunction "TR_P$41") (pintype "bidirectional"))
    )
    (net (code "78") (name "/P2") (class "Default")
      (node (ref "IC3") (pin "B4") (pinfunction "IOT_219_B4") (pintype "bidirectional"))
      (node (ref "TILE2") (pin "P$14") (pinfunction "IDA_P$14") (pintype "bidirectional"))
    )
    (net (code "79") (name "/P3") (class "Default")
      (node (ref "IC3") (pin "A4") (pinfunction "IOT_211_A4") (pintype "bidirectional"))
      (node (ref "TILE2") (pin "P$39") (pinfunction "ICL_P$39") (pintype "bidirectional"))
    )
    (net (code "80") (name "/P4") (class "Default")
      (node (ref "IC3") (pin "D5") (pinfunction "IOT_212_D5") (pintype "bidirectional"))
      (node (ref "TILE2") (pin "P$13") (pinfunction "D10_P$13") (pintype "bidirectional"))
    )
    (net (code "81") (name "/P5") (class "Default")
      (node (ref "IC3") (pin "B5") (pinfunction "IOT_208_B5") (pintype "bidirectional"))
      (node (ref "TILE2") (pin "P$38") (pinfunction "D12_P$38") (pintype "bidirectional"))
    )
    (net (code "82") (name "/P6") (class "Default")
      (node (ref "IC3") (pin "A7") (pinfunction "IOT_192_A7") (pintype "bidirectional"))
      (node (ref "TILE2") (pin "P$12") (pinfunction "D8_P$12") (pintype "bidirectional"))
    )
    (net (code "83") (name "/P7") (class "Default")
      (node (ref "IC3") (pin "B8") (pinfunction "IOT_177_B8") (pintype "bidirectional"))
      (node (ref "TILE2") (pin "P$37") (pinfunction "D9_P$37") (pintype "bidirectional"))
    )
    (net (code "84") (name "/P8") (class "Default")
      (node (ref "IC3") (pin "C9") (pinfunction "IOT_172_C9") (pintype "bidirectional"))
      (node (ref "TILE2") (pin "P$11") (pinfunction "D6_P$11") (pintype "bidirectional"))
    )
    (net (code "85") (name "/P9") (class "Default")
      (node (ref "IC3") (pin "B9") (pinfunction "IOT_174_B9") (pintype "bidirectional"))
      (node (ref "TILE2") (pin "P$36") (pinfunction "D7_P$36") (pintype "bidirectional"))
    )
    (net (code "86") (name "/P10") (class "Default")
      (node (ref "IC3") (pin "A10") (pinfunction "IOT_170_A10") (pintype "bidirectional"))
      (node (ref "TILE2") (pin "P$10") (pinfunction "D4_P$10") (pintype "bidirectional"))
    )
    (net (code "87") (name "/P11") (class "Default")
      (node (ref "IC3") (pin "A11") (pinfunction "IOT_168_A11") (pintype "bidirectional"))
      (node (ref "TILE2") (pin "P$35") (pinfunction "D5_P$35") (pintype "bidirectional"))
    )
    (net (code "88") (name "/P12") (class "Default")
      (node (ref "IC3") (pin "B11") (pinfunction "IOR_161_B11") (pintype "bidirectional"))
      (node (ref "TILE2") (pin "P$9") (pinfunction "D2_P$9") (pintype "bidirectional"))
    )
    (net (code "89") (name "/P13") (class "Default")
      (node (ref "IC3") (pin "C11") (pinfunction "IOR_160_C11") (pintype "bidirectional"))
      (node (ref "TILE2") (pin "P$34") (pinfunction "D3_P$34") (pintype "bidirectional"))
    )
    (net (code "90") (name "/P14") (class "Default")
      (node (ref "IC3") (pin "D10") (pinfunction "IOR_154_D10") (pintype "bidirectional"))
      (node (ref "TILE2") (pin "P$8") (pinfunction "D0_P$8") (pintype "bidirectional"))
    )
    (net (code "91") (name "/P15") (class "Default")
      (node (ref "IC3") (pin "D11") (pinfunction "IOR_152_D11") (pintype "bidirectional"))
      (node (ref "TILE2") (pin "P$33") (pinfunction "D1_P$33") (pintype "bidirectional"))
    )
    (net (code "92") (name "/PEN") (class "Default")
      (node (ref "C13") (pin "1") (pinfunction "1_1") (pintype "passive"))
      (node (ref "IC1") (pin "1") (pinfunction "EN_1") (pintype "input"))
      (node (ref "RN7") (pin "8") (pinfunction "2_8") (pintype "passive"))
    )
    (net (code "93") (name "/PRT") (class "Default")
      (node (ref "IC3") (pin "L9") (pinfunction "CRESET_B_L9") (pintype "bidirectional"))
      (node (ref "IC9") (pin "57") (pinfunction "PD10_57") (pintype "bidirectional"))
    )
    (net (code "94") (name "/QCK") (class "Default")
      (node (ref "IC9") (pin "36") (pinfunction "PB2_36") (pintype "bidirectional"))
      (node (ref "RN5") (pin "4") (pinfunction "1_4") (pintype "passive"))
    )
    (net (code "95") (name "/QCKX") (class "Default")
      (node (ref "IC3") (pin "L8") (pinfunction "IOB_103_CBSEL0_L8") (pintype "bidirectional"))
      (node (ref "RN5") (pin "8") (pinfunction "2_8") (pintype "passive"))
    )
    (net (code "96") (name "/QD0") (class "Default")
      (node (ref "IC9") (pin "58") (pinfunction "PD11_58") (pintype "bidirectional"))
      (node (ref "RN5") (pin "3") (pinfunction "1_3") (pintype "passive"))
    )
    (net (code "97") (name "/QD0X") (class "Default")
      (node (ref "IC3") (pin "H7") (pinfunction "IOB_87_H7") (pintype "bidirectional"))
      (node (ref "RN5") (pin "7") (pinfunction "2_7") (pintype "passive"))
    )
    (net (code "98") (name "/QD1") (class "Default")
      (node (ref "IC9") (pin "59") (pinfunction "PD12_59") (pintype "bidirectional"))
      (node (ref "RN5") (pin "2") (pinfunction "1_2") (pintype "passive"))
    )
    (net (code "99") (name "/QD1X") (class "Default")
      (node (ref "IC3") (pin "K7") (pinfunction "IOB_89_K7") (pintype "bidirectional"))
      (node (ref "RN4") (pin "5") (pinfunction "2_5") (pintype "passive"))
    )
    (net (code "100") (name "/QD2") (class "Default")
      (node (ref "IC9") (pin "1") (pinfunction "PE2_1") (pintype "bidirectional"))
      (node (ref "RN4") (pin "4") (pinfunction "1_4") (pintype "passive"))
    )
    (net (code "101") (name "/QD2X") (class "Default")
      (node (ref "IC3") (pin "J8") (pinfunction "IOB_91_J8") (pintype "bidirectional"))
      (node (ref "RN5") (pin "6") (pinfunction "2_6") (pintype "passive"))
    )
    (net (code "102") (name "/QD3") (class "Default")
      (node (ref "IC9") (pin "60") (pinfunction "PD13_60") (pintype "bidirectional"))
      (node (ref "RN5") (pin "1") (pinfunction "1_1") (pintype "passive"))
    )
    (net (code "103") (name "/QD3X") (class "Default")
      (node (ref "IC3") (pin "L7") (pinfunction "IOB_94_L7") (pintype "bidirectional"))
      (node (ref "RN4") (pin "6") (pinfunction "2_6") (pintype "passive"))
    )
    (net (code "104") (name "/QDR") (class "Default")
      (node (ref "IC3") (pin "J7") (pinfunction "**IOB_86_J7") (pintype "bidirectional"))
      (node (ref "IC9") (pin "62") (pinfunction "PD15_62") (pintype "bidirectional"))
    )
    (net (code "105") (name "/RX") (class "Default")
      (node (ref "IC9") (pin "68") (pinfunction "PA9_68") (pintype "bidirectional"))
      (node (ref "RN1") (pin "1") (pinfunction "1_1") (pintype "passive"))
      (node (ref "TILE6") (pin "E1") (pinfunction "E1_E1") (pintype "bidirectional"))
    )
    (net (code "106") (name "/RXX") (class "Default")
      (node (ref "IC3") (pin "J2") (pinfunction "IOL_25B_J2") (pintype "bidirectional"))
      (node (ref "RN1") (pin "8") (pinfunction "2_8") (pintype "passive"))
    )
    (net (code "107") (name "/R{slash}~{DS}") (class "Default")
      (node (ref "IC3") (pin "B6") (pinfunction "IOT_198_GBIN0_B6") (pintype "bidirectional"))
      (node (ref "TILE6") (pin "F24") (pinfunction "F24_F24") (pintype "bidirectional"))
    )
    (net (code "108") (name "/SCD") (class "Default")
      (node (ref "IC9") (pin "83") (pinfunction "PD2_83") (pintype "bidirectional"))
      (node (ref "RN101") (pin "2") (pinfunction "1_2") (pintype "passive"))
      (node (ref "SD100") (pin "P$7") (pinfunction "CMD/DI_P$7") (pintype "bidirectional"))
    )
    (net (code "109") (name "/SCK") (class "Default")
      (node (ref "IC3") (pin "L10") (pinfunction "IOB_107_SCK_L10") (pintype "bidirectional"))
      (node (ref "IC4") (pin "6") (pinfunction "SCK_6") (pintype "bidirectional"))
      (node (ref "IC9") (pin "42") (pinfunction "PE12_42") (pintype "bidirectional"))
      (node (ref "RN102") (pin "3") (pinfunction "1_3") (pintype "passive"))
      (node (ref "TILE6") (pin "F3") (pinfunction "F3_F3") (pintype "bidirectional"))
    )
    (net (code "110") (name "/SCL") (class "Default")
      (node (ref "IC10") (pin "6") (pinfunction "SCL_6") (pintype "bidirectional"))
      (node (ref "IC9") (pin "46") (pinfunction "PB10_46") (pintype "bidirectional"))
      (node (ref "RN6") (pin "8") (pinfunction "2_8") (pintype "passive"))
      (node (ref "TILE3") (pin "P$39") (pinfunction "ICL_P$39") (pintype "bidirectional"))
      (node (ref "TILE5") (pin "P$39") (pinfunction "ICL_P$39") (pintype "bidirectional"))
      (node (ref "TILE6") (pin "F20") (pinfunction "F20_F20") (pintype "bidirectional"))
    )
    (net (code "111") (name "/SCL2") (class "Default")
      (node (ref "IC9") (pin "95") (pinfunction "PB8_95") (pintype "bidirectional"))
      (node (ref "J1") (pin "4") (pinfunction "4_4") (pintype "passive"))
      (node (ref "RN7") (pin "7") (pinfunction "2_7") (pintype "passive"))
      (node (ref "TILE1") (pin "P$39") (pinfunction "ICL_P$39") (pintype "bidirectional"))
      (node (ref "TILE4") (pin "P$39") (pinfunction "ICL_P$39") (pintype "bidirectional"))
      (node (ref "TILE6") (pin "E20") (pinfunction "E20_E20") (pintype "bidirectional"))
    )
    (net (code "112") (name "/SD") (class "Default")
      (node (ref "IC9") (pin "77") (pinfunction "PA15_77") (pintype "bidirectional"))
      (node (ref "RN100") (pin "1") (pinfunction "1_1") (pintype "passive"))
      (node (ref "SD100") (pin "P$1") (pinfunction "CD_P$1") (pintype "bidirectional"))
    )
    (net (code "113") (name "/SD0") (class "Default")
      (node (ref "IC9") (pin "65") (pinfunction "PC8_65") (pintype "bidirectional"))
      (node (ref "RN100") (pin "3") (pinfunction "1_3") (pintype "passive"))
      (node (ref "SD100") (pin "P$3") (pinfunction "D0/DO_P$3") (pintype "bidirectional"))
    )
    (net (code "114") (name "/SD1") (class "Default")
      (node (ref "IC9") (pin "66") (pinfunction "PC9_66") (pintype "bidirectional"))
      (node (ref "RN100") (pin "2") (pinfunction "1_2") (pintype "passive"))
      (node (ref "SD100") (pin "P$2") (pinfunction "D1_P$2") (pintype "bidirectional"))
    )
    (net (code "115") (name "/SD2") (class "Default")
      (node (ref "IC9") (pin "78") (pinfunction "PC10_78") (pintype "bidirectional"))
      (node (ref "RN101") (pin "4") (pinfunction "1_4") (pintype "passive"))
      (node (ref "SD100") (pin "P$9") (pinfunction "D2_P$9") (pintype "bidirectional"))
    )
    (net (code "116") (name "/SD3") (class "Default")
      (node (ref "IC9") (pin "79") (pinfunction "PC11_79") (pintype "bidirectional"))
      (node (ref "RN101") (pin "3") (pinfunction "1_3") (pintype "passive"))
      (node (ref "SD100") (pin "P$8") (pinfunction "CD/D3_P$8") (pintype "bidirectional"))
    )
    (net (code "117") (name "/SDA") (class "Default")
      (node (ref "IC10") (pin "7") (pinfunction "SDA_7") (pintype "bidirectional"))
      (node (ref "IC9") (pin "47") (pinfunction "PB11_47") (pintype "bidirectional"))
      (node (ref "RN6") (pin "7") (pinfunction "2_7") (pintype "passive"))
      (node (ref "TILE3") (pin "P$14") (pinfunction "IDA_P$14") (pintype "bidirectional"))
      (node (ref "TILE5") (pin "P$14") (pinfunction "IDA_P$14") (pintype "bidirectional"))
      (node (ref "TILE6") (pin "F5") (pinfunction "F5_F5") (pintype "bidirectional"))
    )
    (net (code "118") (name "/SDA2") (class "Default")
      (node (ref "IC9") (pin "96") (pinfunction "PB9_96") (pintype "bidirectional"))
      (node (ref "J1") (pin "3") (pinfunction "3_3") (pintype "passive"))
      (node (ref "RN7") (pin "6") (pinfunction "2_6") (pintype "passive"))
      (node (ref "TILE1") (pin "P$14") (pinfunction "IDA_P$14") (pintype "bidirectional"))
      (node (ref "TILE4") (pin "P$14") (pinfunction "IDA_P$14") (pintype "bidirectional"))
      (node (ref "TILE6") (pin "E5") (pinfunction "E5_E5") (pintype "bidirectional"))
    )
    (net (code "119") (name "/SDK") (class "Default")
      (node (ref "IC9") (pin "80") (pinfunction "PC12_80") (pintype "bidirectional"))
      (node (ref "RN101") (pin "1") (pinfunction "1_1") (pintype "passive"))
      (node (ref "SD100") (pin "P$5") (pinfunction "CLK_P$5") (pintype "bidirectional"))
    )
    (net (code "120") (name "/SHA") (class "Default")
      (node (ref "CN1") (pin "P$1") (pinfunction "SHLD_P$1") (pintype "passive"))
      (node (ref "CN1") (pin "P$2") (pinfunction "SHLD_P$2") (pintype "passive"))
      (node (ref "CN1") (pin "P$3") (pinfunction "SHLD_P$3") (pintype "passive"))
      (node (ref "CN1") (pin "P$4") (pinfunction "SHLD_P$4") (pintype "passive"))
      (node (ref "R8") (pin "1") (pinfunction "1_1") (pintype "passive"))
    )
    (net (code "121") (name "/SHB") (class "Default")
      (node (ref "CN2") (pin "P$1") (pinfunction "SHLD_P$1") (pintype "passive"))
      (node (ref "CN2") (pin "P$2") (pinfunction "SHLD_P$2") (pintype "passive"))
      (node (ref "CN2") (pin "P$3") (pinfunction "SHLD_P$3") (pintype "passive"))
      (node (ref "CN2") (pin "P$4") (pinfunction "SHLD_P$4") (pintype "passive"))
      (node (ref "RN8") (pin "4") (pinfunction "1_4") (pintype "passive"))
    )
    (net (code "122") (name "/SI") (class "Default")
      (node (ref "IC3") (pin "K9") (pinfunction "IOB_105_SDO_K9") (pintype "bidirectional"))
      (node (ref "IC4") (pin "5") (pinfunction "SI_5") (pintype "bidirectional"))
      (node (ref "IC9") (pin "44") (pinfunction "PE14_44") (pintype "bidirectional"))
      (node (ref "RN102") (pin "1") (pinfunction "1_1") (pintype "passive"))
      (node (ref "TILE6") (pin "F21") (pinfunction "F21_F21") (pintype "bidirectional"))
    )
    (net (code "123") (name "/SO") (class "Default")
      (node (ref "IC3") (pin "J9") (pinfunction "IOB_106_SDI_J9") (pintype "bidirectional"))
      (node (ref "IC4") (pin "2") (pinfunction "SO_2") (pintype "bidirectional"))
      (node (ref "IC9") (pin "43") (pinfunction "PE13_43") (pintype "bidirectional"))
      (node (ref "RN102") (pin "2") (pinfunction "1_2") (pintype "passive"))
      (node (ref "TILE6") (pin "F4") (pinfunction "F4_F4") (pintype "bidirectional"))
    )
    (net (code "124") (name "/SWCLK") (class "Default")
      (node (ref "CN3") (pin "9") (pinfunction "9_9") (pintype "bidirectional"))
      (node (ref "IC9") (pin "76") (pinfunction "PA14_76") (pintype "bidirectional"))
      (node (ref "TILE6") (pin "E8") (pinfunction "E8_E8") (pintype "bidirectional"))
    )
    (net (code "125") (name "/SWDIO") (class "Default")
      (node (ref "CN3") (pin "10") (pinfunction "10_10") (pintype "bidirectional"))
      (node (ref "IC9") (pin "72") (pinfunction "PA13_72") (pintype "bidirectional"))
      (node (ref "TILE6") (pin "E7") (pinfunction "E7_E7") (pintype "bidirectional"))
    )
    (net (code "126") (name "/SWO") (class "Default")
      (node (ref "CN3") (pin "8") (pinfunction "8_8") (pintype "bidirectional"))
      (node (ref "IC9") (pin "89") (pinfunction "PB3_89") (pintype "bidirectional"))
      (node (ref "TILE6") (pin "E18") (pinfunction "E18_E18") (pintype "bidirectional"))
    )
    (net (code "127") (name "/TB0") (class "Default")
      (node (ref "IC3") (pin "B1") (pinfunction "IOL_2A_B1") (pintype "bidirectional"))
      (node (ref "TILE1") (pin "P$8") (pinfunction "D0_P$8") (pintype "bidirectional"))
    )
    (net (code "128") (name "/TB1") (class "Default")
      (node (ref "IC3") (pin "B2") (pinfunction "IOL_2B_B2") (pintype "bidirectional"))
      (node (ref "TILE1") (pin "P$33") (pinfunction "D1_P$33") (pintype "bidirectional"))
    )
    (net (code "129") (name "/TB2") (class "Default")
      (node (ref "IC3") (pin "C4") (pinfunction "IOL_4A_C4") (pintype "bidirectional"))
      (node (ref "TILE1") (pin "P$9") (pinfunction "D2_P$9") (pintype "bidirectional"))
    )
    (net (code "130") (name "/TB3") (class "Default")
      (node (ref "IC3") (pin "C3") (pinfunction "IOL_4B_C3") (pintype "bidirectional"))
      (node (ref "TILE1") (pin "P$34") (pinfunction "D3_P$34") (pintype "bidirectional"))
    )
    (net (code "131") (name "/TB4") (class "Default")
      (node (ref "IC3") (pin "C2") (pinfunction "IOL_5A_C2") (pintype "bidirectional"))
      (node (ref "TILE1") (pin "P$10") (pinfunction "D4_P$10") (pintype "bidirectional"))
    )
    (net (code "132") (name "/TB5") (class "Default")
      (node (ref "IC3") (pin "C1") (pinfunction "IOL_5B_C1") (pintype "bidirectional"))
      (node (ref "TILE1") (pin "P$35") (pinfunction "D5_P$35") (pintype "bidirectional"))
    )
    (net (code "133") (name "/TB6") (class "Default")
      (node (ref "IC3") (pin "E1") (pinfunction "IOL_8A_E1") (pintype "bidirectional"))
      (node (ref "TILE1") (pin "P$11") (pinfunction "D6_P$11") (pintype "bidirectional"))
    )
    (net (code "134") (name "/TB7") (class "Default")
      (node (ref "IC3") (pin "D1") (pinfunction "IOL_8B_D1") (pintype "bidirectional"))
      (node (ref "TILE1") (pin "P$36") (pinfunction "D7_P$36") (pintype "bidirectional"))
    )
    (net (code "135") (name "/TB8") (class "Default")
      (node (ref "IC3") (pin "D2") (pinfunction "IOL_9A_D2") (pintype "bidirectional"))
      (node (ref "TILE1") (pin "P$12") (pinfunction "D8_P$12") (pintype "bidirectional"))
    )
    (net (code "136") (name "/TB9") (class "Default")
      (node (ref "IC3") (pin "D3") (pinfunction "IOL_9B_D3") (pintype "bidirectional"))
      (node (ref "TILE1") (pin "P$37") (pinfunction "D9_P$37") (pintype "bidirectional"))
    )
    (net (code "137") (name "/TB10") (class "Default")
      (node (ref "IC3") (pin "E2") (pinfunction "IOL_10A_E2") (pintype "bidirectional"))
      (node (ref "TILE1") (pin "P$13") (pinfunction "D10_P$13") (pintype "bidirectional"))
    )
    (net (code "138") (name "/TB11") (class "Default")
      (node (ref "IC3") (pin "E3") (pinfunction "IOL_10B_E3") (pintype "bidirectional"))
      (node (ref "TILE1") (pin "P$38") (pinfunction "D12_P$38") (pintype "bidirectional"))
    )
    (net (code "139") (name "/TC0") (class "Default")
      (node (ref "IC3") (pin "F1") (pinfunction "IOL_12A_F1") (pintype "bidirectional"))
      (node (ref "TILE4") (pin "P$8") (pinfunction "D0_P$8") (pintype "bidirectional"))
    )
    (net (code "140") (name "/TC1") (class "Default")
      (node (ref "IC3") (pin "F2") (pinfunction "IOL_12B_F2") (pintype "bidirectional"))
      (node (ref "TILE4") (pin "P$33") (pinfunction "D1_P$33") (pintype "bidirectional"))
    )
    (net (code "141") (name "/TC2") (class "Default")
      (node (ref "IC3") (pin "F4") (pinfunction "IOL_13A_F4") (pintype "bidirectional"))
      (node (ref "TILE4") (pin "P$9") (pinfunction "D2_P$9") (pintype "bidirectional"))
    )
    (net (code "142") (name "/TC3") (class "Default")
      (node (ref "IC3") (pin "F3") (pinfunction "IOL_13B_GBIN7_F3") (pintype "bidirectional"))
      (node (ref "TILE4") (pin "P$34") (pinfunction "D3_P$34") (pintype "bidirectional"))
    )
    (net (code "143") (name "/TC4") (class "Default")
      (node (ref "IC3") (pin "G1") (pinfunction "IOL_14A_GBIN6_G1") (pintype "bidirectional"))
      (node (ref "TILE4") (pin "P$10") (pinfunction "D4_P$10") (pintype "bidirectional"))
    )
    (net (code "144") (name "/TC5") (class "Default")
      (node (ref "IC3") (pin "G2") (pinfunction "IOL_14B_G2") (pintype "bidirectional"))
      (node (ref "TILE4") (pin "P$35") (pinfunction "D5_P$35") (pintype "bidirectional"))
    )
    (net (code "145") (name "/TC6") (class "Default")
      (node (ref "IC3") (pin "G3") (pinfunction "IOL_17A_G3") (pintype "bidirectional"))
      (node (ref "TILE4") (pin "P$11") (pinfunction "D6_P$11") (pintype "bidirectional"))
    )
    (net (code "146") (name "/TC7") (class "Default")
      (node (ref "IC3") (pin "H3") (pinfunction "IOL_17B_H3") (pintype "bidirectional"))
      (node (ref "TILE4") (pin "P$36") (pinfunction "D7_P$36") (pintype "bidirectional"))
    )
    (net (code "147") (name "/TC8") (class "Default")
      (node (ref "IC3") (pin "H1") (pinfunction "IOL_18A_H1") (pintype "bidirectional"))
      (node (ref "TILE4") (pin "P$12") (pinfunction "D8_P$12") (pintype "bidirectional"))
    )
    (net (code "148") (name "/TC9") (class "Default")
      (node (ref "IC3") (pin "H2") (pinfunction "IOL_18B_H2") (pintype "bidirectional"))
      (node (ref "TILE4") (pin "P$37") (pinfunction "D9_P$37") (pintype "bidirectional"))
    )
    (net (code "149") (name "/TC10") (class "Default")
      (node (ref "IC3") (pin "J1") (pinfunction "IOL_23A_J1") (pintype "bidirectional"))
      (node (ref "TILE4") (pin "P$13") (pinfunction "D10_P$13") (pintype "bidirectional"))
    )
    (net (code "150") (name "/TC11") (class "Default")
      (node (ref "IC3") (pin "K1") (pinfunction "IOL_23B_K1") (pintype "bidirectional"))
      (node (ref "TILE4") (pin "P$38") (pinfunction "D12_P$38") (pintype "bidirectional"))
    )
    (net (code "151") (name "/TF0") (class "Default")
      (node (ref "IC3") (pin "A9") (pinfunction "IOT_178A_A9") (pintype "bidirectional"))
      (node (ref "TILE3") (pin "P$8") (pinfunction "D0_P$8") (pintype "bidirectional"))
    )
    (net (code "152") (name "/TF1") (class "Default")
      (node (ref "IC3") (pin "C8") (pinfunction "IOT_179B_C8") (pintype "bidirectional"))
      (node (ref "TILE3") (pin "P$33") (pinfunction "D1_P$33") (pintype "bidirectional"))
    )
    (net (code "153") (name "/TF2") (class "Default")
      (node (ref "IC3") (pin "A8") (pinfunction "IOT_190A_A8") (pintype "bidirectional"))
      (node (ref "TILE3") (pin "P$9") (pinfunction "D2_P$9") (pintype "bidirectional"))
    )
    (net (code "154") (name "/TF3") (class "Default")
      (node (ref "IC3") (pin "C7") (pinfunction "IOT_191B_C7") (pintype "bidirectional"))
      (node (ref "TILE3") (pin "P$34") (pinfunction "D3_P$34") (pintype "bidirectional"))
    )
    (net (code "155") (name "/TF4") (class "Default")
      (node (ref "IC3") (pin "A6") (pinfunction "IOT_206A_A6") (pintype "bidirectional"))
      (node (ref "TILE3") (pin "P$10") (pinfunction "D4_P$10") (pintype "bidirectional"))
    )
    (net (code "156") (name "/TF5") (class "Default")
      (node (ref "IC3") (pin "A5") (pinfunction "IOT_207B_A5") (pintype "bidirectional"))
      (node (ref "TILE3") (pin "P$35") (pinfunction "D5_P$35") (pintype "bidirectional"))
    )
    (net (code "157") (name "/TF6") (class "Default")
      (node (ref "IC3") (pin "A2") (pinfunction "IOT_222A_A2") (pintype "bidirectional"))
      (node (ref "TILE3") (pin "P$11") (pinfunction "D6_P$11") (pintype "bidirectional"))
    )
    (net (code "158") (name "/TF7") (class "Default")
      (node (ref "IC3") (pin "A3") (pinfunction "IOT_223B_A3") (pintype "bidirectional"))
      (node (ref "TILE3") (pin "P$36") (pinfunction "D7_P$36") (pintype "bidirectional"))
    )
    (net (code "159") (name "/TF8") (class "Default")
      (node (ref "IC3") (pin "F11") (pinfunction "IOR_140_GBIN3_F11") (pintype "bidirectional"))
      (node (ref "TILE3") (pin "P$12") (pinfunction "D8_P$12") (pintype "bidirectional"))
    )
    (net (code "160") (name "/TF9") (class "Default")
      (node (ref "IC3") (pin "E9") (pinfunction "IOR_144_E9") (pintype "bidirectional"))
      (node (ref "TILE3") (pin "P$37") (pinfunction "D9_P$37") (pintype "bidirectional"))
    )
    (net (code "161") (name "/TF10") (class "Default")
      (node (ref "IC3") (pin "E10") (pinfunction "IOR_141_GBIN2_E10") (pintype "bidirectional"))
      (node (ref "TILE3") (pin "P$13") (pinfunction "D10_P$13") (pintype "bidirectional"))
    )
    (net (code "162") (name "/TF11") (class "Default")
      (node (ref "IC3") (pin "E8") (pinfunction "IOR_146_E8") (pintype "bidirectional"))
      (node (ref "TILE3") (pin "P$38") (pinfunction "D12_P$38") (pintype "bidirectional"))
    )
    (net (code "163") (name "/TG0") (class "Default")
      (node (ref "IC3") (pin "K11") (pinfunction "IOR_115A_K11") (pintype "bidirectional"))
      (node (ref "TILE5") (pin "P$8") (pinfunction "D0_P$8") (pintype "bidirectional"))
    )
    (net (code "164") (name "/TG1") (class "Default")
      (node (ref "IC3") (pin "H10") (pinfunction "IOR_116B_H10") (pintype "bidirectional"))
      (node (ref "TILE5") (pin "P$33") (pinfunction "D1_P$33") (pintype "bidirectional"))
    )
    (net (code "165") (name "/TG2") (class "Default")
      (node (ref "IC3") (pin "J10") (pinfunction "IOR_117A_J10") (pintype "bidirectional"))
      (node (ref "TILE5") (pin "P$9") (pinfunction "D2_P$9") (pintype "bidirectional"))
    )
    (net (code "166") (name "/TG3") (class "Default")
      (node (ref "IC3") (pin "G8") (pinfunction "IOR_118B_G8") (pintype "bidirectional"))
      (node (ref "TILE5") (pin "P$34") (pinfunction "D3_P$34") (pintype "bidirectional"))
    )
    (net (code "167") (name "/TG4") (class "Default")
      (node (ref "IC3") (pin "H11") (pinfunction "IOR_119A_H11") (pintype "bidirectional"))
      (node (ref "TILE5") (pin "P$10") (pinfunction "D4_P$10") (pintype "bidirectional"))
    )
    (net (code "168") (name "/TG5") (class "Default")
      (node (ref "IC3") (pin "G10") (pinfunction "IOR_120B_G10") (pintype "bidirectional"))
      (node (ref "TILE5") (pin "P$35") (pinfunction "D5_P$35") (pintype "bidirectional"))
    )
    (net (code "169") (name "/TG6") (class "Default")
      (node (ref "IC3") (pin "D9") (pinfunction "IOR_147A_D9") (pintype "bidirectional"))
      (node (ref "TILE5") (pin "P$11") (pinfunction "D6_P$11") (pintype "bidirectional"))
    )
    (net (code "170") (name "/TG7") (class "Default")
      (node (ref "IC3") (pin "E11") (pinfunction "IOR_148B_E11") (pintype "bidirectional"))
      (node (ref "TILE5") (pin "P$36") (pinfunction "D7_P$36") (pintype "bidirectional"))
    )
    (net (code "171") (name "/TG8") (class "Default")
      (node (ref "IC3") (pin "G9") (pinfunction "IOR_128_G9") (pintype "bidirectional"))
      (node (ref "TILE5") (pin "P$12") (pinfunction "D8_P$12") (pintype "bidirectional"))
    )
    (net (code "172") (name "/TG9") (class "Default")
      (node (ref "IC3") (pin "G11") (pinfunction "IOR_129_G11") (pintype "bidirectional"))
      (node (ref "TILE5") (pin "P$37") (pinfunction "D9_P$37") (pintype "bidirectional"))
    )
    (net (code "173") (name "/TG10") (class "Default")
      (node (ref "IC3") (pin "F10") (pinfunction "IOR_136_F10") (pintype "bidirectional"))
      (node (ref "TILE5") (pin "P$13") (pinfunction "D10_P$13") (pintype "bidirectional"))
    )
    (net (code "174") (name "/TG11") (class "Default")
      (node (ref "IC3") (pin "F9") (pinfunction "IOR_137_F9") (pintype "bidirectional"))
      (node (ref "TILE5") (pin "P$38") (pinfunction "D12_P$38") (pintype "bidirectional"))
    )
    (net (code "175") (name "/TR1") (class "Default")
      (node (ref "IC9") (pin "52") (pinfunction "PB13_52") (pintype "bidirectional"))
      (node (ref "TILE3") (pin "P$41") (pinfunction "TR_P$41") (pintype "bidirectional"))
    )
    (net (code "176") (name "/TR2") (class "Default")
      (node (ref "IC9") (pin "51") (pinfunction "PB12_51") (pintype "bidirectional"))
      (node (ref "TILE5") (pin "P$41") (pinfunction "TR_P$41") (pintype "bidirectional"))
    )
    (net (code "177") (name "/TR3") (class "Default")
      (node (ref "IC9") (pin "2") (pinfunction "PE3_2") (pintype "bidirectional"))
      (node (ref "TILE4") (pin "P$41") (pinfunction "TR_P$41") (pintype "bidirectional"))
    )
    (net (code "178") (name "/TR4") (class "Default")
      (node (ref "IC9") (pin "7") (pinfunction "PC13-ANTI_TAMP_7") (pintype "bidirectional"))
      (node (ref "TILE1") (pin "P$41") (pinfunction "TR_P$41") (pintype "bidirectional"))
    )
    (net (code "179") (name "/TR5") (class "Default")
      (node (ref "IC9") (pin "55") (pinfunction "PD8_55") (pintype "bidirectional"))
    )
    (net (code "180") (name "/TR6") (class "Default")
      (node (ref "IC9") (pin "56") (pinfunction "PD9_56") (pintype "bidirectional"))
    )
    (net (code "181") (name "/TX") (class "Default")
      (node (ref "IC9") (pin "69") (pinfunction "PA10_69") (pintype "bidirectional"))
      (node (ref "RN1") (pin "2") (pinfunction "1_2") (pintype "passive"))
      (node (ref "TILE6") (pin "E24") (pinfunction "E24_E24") (pintype "bidirectional"))
    )
    (net (code "182") (name "/TXX") (class "Default")
      (node (ref "IC3") (pin "K2") (pinfunction "IOL_25A_K2") (pintype "bidirectional"))
      (node (ref "RN1") (pin "7") (pinfunction "2_7") (pintype "passive"))
    )
    (net (code "183") (name "/VB+") (class "Default")
      (node (ref "C19") (pin "1") (pinfunction "1_1") (pintype "passive"))
      (node (ref "H4") (pin "P$1") (pinfunction "P_P$1") (pintype "bidirectional"))
      (node (ref "TILE1") (pin "P$20") (pinfunction "V+_P$20") (pintype "power_in"))
      (node (ref "TILE1") (pin "P$21") (pinfunction "V+_P$21") (pintype "power_in"))
      (node (ref "TILE1") (pin "P$22") (pinfunction "V+_P$22") (pintype "power_in"))
      (node (ref "TILE1") (pin "P$23") (pinfunction "V+_P$23") (pintype "power_in"))
      (node (ref "TILE1") (pin "P$24") (pinfunction "V+_P$24") (pintype "power_in"))
      (node (ref "TILE1") (pin "P$25") (pinfunction "V+_P$25") (pintype "power_in"))
      (node (ref "TILE1") (pin "P$45") (pinfunction "V+_P$45") (pintype "power_in"))
      (node (ref "TILE1") (pin "P$46") (pinfunction "V+_P$46") (pintype "power_in"))
      (node (ref "TILE1") (pin "P$47") (pinfunction "V+_P$47") (pintype "power_in"))
      (node (ref "TILE1") (pin "P$48") (pinfunction "V+_P$48") (pintype "power_in"))
      (node (ref "TILE1") (pin "P$49") (pinfunction "V+_P$49") (pintype "power_in"))
      (node (ref "TILE1") (pin "P$50") (pinfunction "V+_P$50") (pintype "power_in"))
      (node (ref "TILE2") (pin "P$20") (pinfunction "V+_P$20") (pintype "power_in"))
      (node (ref "TILE2") (pin "P$21") (pinfunction "V+_P$21") (pintype "power_in"))
      (node (ref "TILE2") (pin "P$22") (pinfunction "V+_P$22") (pintype "power_in"))
      (node (ref "TILE2") (pin "P$23") (pinfunction "V+_P$23") (pintype "power_in"))
      (node (ref "TILE2") (pin "P$24") (pinfunction "V+_P$24") (pintype "power_in"))
      (node (ref "TILE2") (pin "P$25") (pinfunction "V+_P$25") (pintype "power_in"))
      (node (ref "TILE2") (pin "P$45") (pinfunction "V+_P$45") (pintype "power_in"))
      (node (ref "TILE2") (pin "P$46") (pinfunction "V+_P$46") (pintype "power_in"))
      (node (ref "TILE2") (pin "P$47") (pinfunction "V+_P$47") (pintype "power_in"))
      (node (ref "TILE2") (pin "P$48") (pinfunction "V+_P$48") (pintype "power_in"))
      (node (ref "TILE2") (pin "P$49") (pinfunction "V+_P$49") (pintype "power_in"))
      (node (ref "TILE2") (pin "P$50") (pinfunction "V+_P$50") (pintype "power_in"))
      (node (ref "TILE3") (pin "P$20") (pinfunction "V+_P$20") (pintype "power_in"))
      (node (ref "TILE3") (pin "P$21") (pinfunction "V+_P$21") (pintype "power_in"))
      (node (ref "TILE3") (pin "P$22") (pinfunction "V+_P$22") (pintype "power_in"))
      (node (ref "TILE3") (pin "P$23") (pinfunction "V+_P$23") (pintype "power_in"))
      (node (ref "TILE3") (pin "P$24") (pinfunction "V+_P$24") (pintype "power_in"))
      (node (ref "TILE3") (pin "P$25") (pinfunction "V+_P$25") (pintype "power_in"))
      (node (ref "TILE3") (pin "P$45") (pinfunction "V+_P$45") (pintype "power_in"))
      (node (ref "TILE3") (pin "P$46") (pinfunction "V+_P$46") (pintype "power_in"))
      (node (ref "TILE3") (pin "P$47") (pinfunction "V+_P$47") (pintype "power_in"))
      (node (ref "TILE3") (pin "P$48") (pinfunction "V+_P$48") (pintype "power_in"))
      (node (ref "TILE3") (pin "P$49") (pinfunction "V+_P$49") (pintype "power_in"))
      (node (ref "TILE3") (pin "P$50") (pinfunction "V+_P$50") (pintype "power_in"))
      (node (ref "TILE4") (pin "P$20") (pinfunction "V+_P$20") (pintype "power_in"))
      (node (ref "TILE4") (pin "P$21") (pinfunction "V+_P$21") (pintype "power_in"))
      (node (ref "TILE4") (pin "P$22") (pinfunction "V+_P$22") (pintype "power_in"))
      (node (ref "TILE4") (pin "P$23") (pinfunction "V+_P$23") (pintype "power_in"))
      (node (ref "TILE4") (pin "P$24") (pinfunction "V+_P$24") (pintype "power_in"))
      (node (ref "TILE4") (pin "P$25") (pinfunction "V+_P$25") (pintype "power_in"))
      (node (ref "TILE4") (pin "P$45") (pinfunction "V+_P$45") (pintype "power_in"))
      (node (ref "TILE4") (pin "P$46") (pinfunction "V+_P$46") (pintype "power_in"))
      (node (ref "TILE4") (pin "P$47") (pinfunction "V+_P$47") (pintype "power_in"))
      (node (ref "TILE4") (pin "P$48") (pinfunction "V+_P$48") (pintype "power_in"))
      (node (ref "TILE4") (pin "P$49") (pinfunction "V+_P$49") (pintype "power_in"))
      (node (ref "TILE4") (pin "P$50") (pinfunction "V+_P$50") (pintype "power_in"))
      (node (ref "TILE5") (pin "P$20") (pinfunction "V+_P$20") (pintype "power_in"))
      (node (ref "TILE5") (pin "P$21") (pinfunction "V+_P$21") (pintype "power_in"))
      (node (ref "TILE5") (pin "P$22") (pinfunction "V+_P$22") (pintype "power_in"))
      (node (ref "TILE5") (pin "P$23") (pinfunction "V+_P$23") (pintype "power_in"))
      (node (ref "TILE5") (pin "P$24") (pinfunction "V+_P$24") (pintype "power_in"))
      (node (ref "TILE5") (pin "P$25") (pinfunction "V+_P$25") (pintype "power_in"))
      (node (ref "TILE5") (pin "P$45") (pinfunction "V+_P$45") (pintype "power_in"))
      (node (ref "TILE5") (pin "P$46") (pinfunction "V+_P$46") (pintype "power_in"))
      (node (ref "TILE5") (pin "P$47") (pinfunction "V+_P$47") (pintype "power_in"))
      (node (ref "TILE5") (pin "P$48") (pinfunction "V+_P$48") (pintype "power_in"))
      (node (ref "TILE5") (pin "P$49") (pinfunction "V+_P$49") (pintype "power_in"))
      (node (ref "TILE5") (pin "P$50") (pinfunction "V+_P$50") (pintype "power_in"))
      (node (ref "TILE6") (pin "F13") (pinfunction "F13_F13") (pintype "bidirectional"))
      (node (ref "TILE6") (pin "F14") (pinfunction "F14_F14") (pintype "bidirectional"))
      (node (ref "TILE6") (pin "F15") (pinfunction "F15_F15") (pintype "bidirectional"))
      (node (ref "TILE6") (pin "F16") (pinfunction "F16_F16") (pintype "bidirectional"))
      (node (ref "TILE6") (pin "F17") (pinfunction "F17_F17") (pintype "bidirectional"))
      (node (ref "TILE6") (pin "F18") (pinfunction "F18_F18") (pintype "bidirectional"))
      (node (ref "U$1") (pin "C") (pinfunction "CATHODE_C") (pintype "passive"))
    )
    (net (code "184") (name "/VBAT") (class "Default")
      (node (ref "BT100") (pin "1") (pinfunction "+_1") (pintype "power_in"))
      (node (ref "C23") (pin "1") (pinfunction "1_1") (pintype "passive"))
      (node (ref "IC9") (pin "6") (pinfunction "VBAT_6") (pintype "bidirectional"))
    )
    (net (code "185") (name "/VBUSA") (class "Default")
      (node (ref "CN1") (pin "VBUS@1") (pinfunction "VBUS_VBUS@1") (pintype "power_in"))
      (node (ref "CN1") (pin "VBUS@2") (pinfunction "VBUS_VBUS@2") (pintype "power_in"))
      (node (ref "IC8") (pin "5") (pinfunction "VBUS_5") (pintype "bidirectional"))
      (node (ref "TILE6") (pin "E15") (pinfunction "E15_E15") (pintype "bidirectional"))
      (node (ref "U$2") (pin "A") (pinfunction "ANODE_A") (pintype "passive"))
    )
    (net (code "186") (name "/VBUSB") (class "Default")
      (node (ref "CN2") (pin "VBUS@1") (pinfunction "VBUS_VBUS@1") (pintype "power_in"))
      (node (ref "CN2") (pin "VBUS@2") (pinfunction "VBUS_VBUS@2") (pintype "power_in"))
      (node (ref "IC10") (pin "2") (pinfunction "VBUS_2") (pintype "bidirectional"))
      (node (ref "U$1") (pin "A") (pinfunction "ANODE_A") (pintype "passive"))
    )
    (net (code "187") (name "/VCC") (class "Default")
      (node (ref "C107") (pin "2") (pinfunction "2_2") (pintype "passive"))
      (node (ref "C109") (pin "2") (pinfunction "2_2") (pintype "passive"))
      (node (ref "C110") (pin "2") (pinfunction "2_2") (pintype "passive"))
      (node (ref "C4") (pin "1") (pinfunction "1_1") (pintype "passive"))
      (node (ref "C5") (pin "2") (pinfunction "2_2") (pintype "passive"))
      (node (ref "I1") (pin "P$2") (pinfunction "P$2_P$2") (pintype "passive"))
      (node (ref "IC3") (pin "D4") (pinfunction "VCC_1_D4") (pintype "bidirectional"))
      (node (ref "IC3") (pin "D8") (pinfunction "VCC_2_D8") (pintype "bidirectional"))
      (node (ref "IC3") (pin "H4") (pinfunction "VCC_3_H4") (pintype "bidirectional"))
      (node (ref "IC3") (pin "H8") (pinfunction "VCC_4_H8") (pintype "bidirectional"))
      (node (ref "R2") (pin "2") (pinfunction "2_2") (pintype "passive"))
      (node (ref "R3") (pin "1") (pinfunction "1_1") (pintype "passive"))
      (node (ref "R4") (pin "2") (pinfunction "2_2") (pintype "passive"))
    )
    (net (code "188") (name "/VPLL0") (class "Default")
      (node (ref "C104") (pin "2") (pinfunction "2_2") (pintype "passive"))
      (node (ref "C105") (pin "2") (pinfunction "2_2") (pintype "passive"))
      (node (ref "IC3") (pin "J6") (pinfunction "VCCPLL0_J6") (pintype "bidirectional"))
      (node (ref "R4") (pin "1") (pinfunction "1_1") (pintype "passive"))
    )
    (net (code "189") (name "/VPLL1") (class "Default")
      (node (ref "C111") (pin "2") (pinfunction "2_2") (pintype "passive"))
      (node (ref "C113") (pin "2") (pinfunction "2_2") (pintype "passive"))
      (node (ref "IC3") (pin "C6") (pinfunction "VCCPLL1_C6") (pintype "bidirectional"))
      (node (ref "R3") (pin "2") (pinfunction "2_2") (pintype "passive"))
    )
    (net (code "190") (name "/WP") (class "Default")
      (node (ref "IC4") (pin "3") (pinfunction "WP_3") (pintype "bidirectional"))
      (node (ref "IC9") (pin "40") (pinfunction "PE10_40") (pintype "bidirectional"))
    )
    (net (code "191") (name "/~{HRST}") (class "Default")
      (node (ref "IC6") (pin "A4") (pinfunction "RESET#_A4") (pintype "bidirectional"))
      (node (ref "IC9") (pin "81") (pinfunction "PD0_81") (pintype "bidirectional"))
    )
    (net (code "192") (name "/~{QSSX}") (class "Default")
      (node (ref "IC3") (pin "H9") (pinfunction "IOB_104_CBSEL1_H9") (pintype "bidirectional"))
      (node (ref "RN5") (pin "5") (pinfunction "2_5") (pintype "passive"))
    )
    (net (code "193") (name "/~{QSS}") (class "Default")
      (node (ref "IC9") (pin "92") (pinfunction "PB6_92") (pintype "bidirectional"))
      (node (ref "RN4") (pin "3") (pinfunction "1_3") (pintype "passive"))
    )
    (net (code "194") (name "/~{SRST}") (class "Default")
      (node (ref "C24") (pin "2") (pinfunction "2_2") (pintype "passive"))
      (node (ref "CN3") (pin "6") (pinfunction "6_6") (pintype "bidirectional"))
      (node (ref "IC9") (pin "14") (pinfunction "NRST_14") (pintype "bidirectional"))
      (node (ref "RN7") (pin "5") (pinfunction "2_5") (pintype "passive"))
      (node (ref "TILE6") (pin "E17") (pinfunction "E17_E17") (pintype "bidirectional"))
    )
    (net (code "195") (name "/~{SS}") (class "Default")
      (node (ref "IC3") (pin "K10") (pinfunction "IOB_108_SS_K10") (pintype "bidirectional"))
      (node (ref "IC4") (pin "1") (pinfunction "CS_1") (pintype "input"))
      (node (ref "IC9") (pin "41") (pinfunction "PE11_41") (pintype "bidirectional"))
      (node (ref "RN102") (pin "4") (pinfunction "1_4") (pintype "passive"))
    )
    (net (code "196") (name "/~{TRSTA}") (class "Default")
      (node (ref "IC9") (pin "97") (pinfunction "PE0_97") (pintype "bidirectional"))
      (node (ref "TILE1") (pin "P$15") (pinfunction "PRG/RS_P$15") (pintype "open_collector"))
      (node (ref "TILE2") (pin "P$15") (pinfunction "PRG/RS_P$15") (pintype "open_collector"))
      (node (ref "TILE4") (pin "P$15") (pinfunction "PRG/RS_P$15") (pintype "open_collector"))
    )
    (net (code "197") (name "/~{TRSTB}") (class "Default")
      (node (ref "IC9") (pin "37") (pinfunction "PE7_37") (pintype "bidirectional"))
      (node (ref "TILE3") (pin "P$15") (pinfunction "PRG/RS_P$15") (pintype "open_collector"))
      (node (ref "TILE5") (pin "P$15") (pinfunction "PRG/RS_P$15") (pintype "open_collector"))
    )
    (net (code "198") (name "GND") (class "Default")
      (node (ref "BT100") (pin "2") (pinfunction "-_2") (pintype "power_in"))
      (node (ref "C1") (pin "1") (pinfunction "1_1") (pintype "passive"))
      (node (ref "C10") (pin "2") (pinfunction "2_2") (pintype "passive"))
      (node (ref "C100") (pin "2") (pinfunction "2_2") (pintype "passive"))
      (node (ref "C101") (pin "1") (pinfunction "1_1") (pintype "passive"))
      (node (ref "C102") (pin "2") (pinfunction "2_2") (pintype "passive"))
      (node (ref "C103") (pin "2") (pinfunction "2_2") (pintype "passive"))
      (node (ref "C106") (pin "2") (pinfunction "2_2") (pintype "passive"))
      (node (ref "C107") (pin "1") (pinfunction "1_1") (pintype "passive"))
      (node (ref "C108") (pin "2") (pinfunction "2_2") (pintype "passive"))
      (node (ref "C109") (pin "1") (pinfunction "1_1") (pintype "passive"))
      (node (ref "C110") (pin "1") (pinfunction "1_1") (pintype "passive"))
      (node (ref "C112") (pin "2") (pinfunction "2_2") (pintype "passive"))
      (node (ref "C12") (pin "2") (pinfunction "2_2") (pintype "passive"))
      (node (ref "C13") (pin "2") (pinfunction "2_2") (pintype "passive"))
      (node (ref "C14") (pin "1") (pinfunction "1_1") (pintype "passive"))
      (node (ref "C15") (pin "2") (pinfunction "2_2") (pintype "passive"))
      (node (ref "C16") (pin "1") (pinfunction "1_1") (pintype "passive"))
      (node (ref "C17") (pin "1") (pinfunction "1_1") (pintype "passive"))
      (node (ref "C18") (pin "1") (pinfunction "1_1") (pintype "passive"))
      (node (ref "C19") (pin "2") (pinfunction "2_2") (pintype "passive"))
      (node (ref "C2") (pin "2") (pinfunction "2_2") (pintype "passive"))
      (node (ref "C20") (pin "2") (pinfunction "2_2") (pintype "passive"))
      (node (ref "C21") (pin "1") (pinfunction "1_1") (pintype "passive"))
      (node (ref "C22") (pin "1") (pinfunction "1_1") (pintype "passive"))
      (node (ref "C23") (pin "2") (pinfunction "2_2") (pintype "passive"))
      (node (ref "C24") (pin "1") (pinfunction "1_1") (pintype "passive"))
      (node (ref "C25") (pin "2") (pinfunction "2_2") (pintype "passive"))
      (node (ref "C26") (pin "1") (pinfunction "1_1") (pintype "passive"))
      (node (ref "C27") (pin "1") (pinfunction "1_1") (pintype "passive"))
      (node (ref "C28") (pin "1") (pinfunction "1_1") (pintype "passive"))
      (node (ref "C29") (pin "1") (pinfunction "1_1") (pintype "passive"))
      (node (ref "C3") (pin "1") (pinfunction "1_1") (pintype "passive"))
      (node (ref "C31") (pin "1") (pinfunction "1_1") (pintype "passive"))
      (node (ref "C32") (pin "1") (pinfunction "1_1") (pintype "passive"))
      (node (ref "C33") (pin "2") (pinfunction "2_2") (pintype "passive"))
      (node (ref "C34") (pin "1") (pinfunction "1_1") (pintype "passive"))
      (node (ref "C4") (pin "2") (pinfunction "2_2") (pintype "passive"))
      (node (ref "C6") (pin "1") (pinfunction "1_1") (pintype "passive"))
      (node (ref "C7") (pin "1") (pinfunction "1_1") (pintype "passive"))
      (node (ref "C8") (pin "1") (pinfunction "1_1") (pintype "passive"))
      (node (ref "C9") (pin "2") (pinfunction "2_2") (pintype "passive"))
      (node (ref "CN1") (pin "GND@1") (pinfunction "GND_GND@1") (pintype "power_in"))
      (node (ref "CN1") (pin "GND@2") (pinfunction "GND_GND@2") (pintype "power_in"))
      (node (ref "CN2") (pin "GND@1") (pinfunction "GND_GND@1") (pintype "power_in"))
      (node (ref "CN2") (pin "GND@2") (pinfunction "GND_GND@2") (pintype "power_in"))
      (node (ref "CN3") (pin "2") (pinfunction "2_2") (pintype "bidirectional"))
      (node (ref "CN3") (pin "3") (pinfunction "3_3") (pintype "bidirectional"))
      (node (ref "CN3") (pin "5") (pinfunction "5_5") (pintype "bidirectional"))
      (node (ref "H3") (pin "P$1") (pinfunction "P_P$1") (pintype "bidirectional"))
      (node (ref "IC1") (pin "2") (pinfunction "GND_2") (pintype "power_in"))
      (node (ref "IC10") (pin "8") (pinfunction "GND_1_8") (pintype "bidirectional"))
      (node (ref "IC10") (pin "9") (pinfunction "GND_2_9") (pintype "bidirectional"))
      (node (ref "IC2") (pin "2") (pinfunction "GND_2") (pintype "power_in"))
      (node (ref "IC3") (pin "E5") (pinfunction "GND_1_E5") (pintype "bidirectional"))
      (node (ref "IC3") (pin "E6") (pinfunction "GND_2_E6") (pintype "bidirectional"))
      (node (ref "IC3") (pin "E7") (pinfunction "GND_3_E7") (pintype "bidirectional"))
      (node (ref "IC3") (pin "F5") (pinfunction "GND_4_F5") (pintype "bidirectional"))
      (node (ref "IC3") (pin "F6") (pinfunction "GND_5_F6") (pintype "bidirectional"))
      (node (ref "IC3") (pin "F7") (pinfunction "GND_6_F7") (pintype "bidirectional"))
      (node (ref "IC3") (pin "G5") (pinfunction "GND_7_G5") (pintype "bidirectional"))
      (node (ref "IC3") (pin "G6") (pinfunction "GND_8_G6") (pintype "bidirectional"))
      (node (ref "IC3") (pin "G7") (pinfunction "GND_9_G7") (pintype "bidirectional"))
      (node (ref "IC3") (pin "H5") (pinfunction "GND_10_H5") (pintype "bidirectional"))
      (node (ref "IC4") (pin "4") (pinfunction "GND_4") (pintype "power_in"))
      (node (ref "IC5") (pin "2") (pinfunction "GND_2") (pintype "power_in"))
      (node (ref "IC6") (pin "B3") (pinfunction "VSS_B3") (pintype "bidirectional"))
      (node (ref "IC6") (pin "C1") (pinfunction "VSSQ_1_C1") (pintype "bidirectional"))
      (node (ref "IC6") (pin "E5") (pinfunction "VSSQ_2_E5") (pintype "bidirectional"))
      (node (ref "IC7") (pin "2") (pinfunction "GND_2") (pintype "bidirectional"))
      (node (ref "IC8") (pin "2") (pinfunction "GND_2") (pintype "bidirectional"))
      (node (ref "IC9") (pin "19") (pinfunction "VSSA_19") (pintype "bidirectional"))
      (node (ref "IC9") (pin "26") (pinfunction "VSS_2_26") (pintype "bidirectional"))
      (node (ref "IC9") (pin "49") (pinfunction "VSS_3_49") (pintype "bidirectional"))
      (node (ref "IC9") (pin "74") (pinfunction "VSS_4_74") (pintype "bidirectional"))
      (node (ref "J1") (pin "1") (pinfunction "1_1") (pintype "power_in"))
      (node (ref "L2") (pin "C") (pinfunction "C_C") (pintype "passive"))
      (node (ref "R1") (pin "2") (pinfunction "2_2") (pintype "passive"))
      (node (ref "R6") (pin "2") (pinfunction "2_2") (pintype "passive"))
      (node (ref "R8") (pin "2") (pinfunction "2_2") (pintype "passive"))
      (node (ref "RN100") (pin "4") (pinfunction "1_4") (pintype "passive"))
      (node (ref "RN8") (pin "5") (pinfunction "2_5") (pintype "passive"))
      (node (ref "RN9") (pin "1") (pinfunction "1_1") (pintype "passive"))
      (node (ref "RN9") (pin "2") (pinfunction "1_2") (pintype "passive"))
      (node (ref "SD100") (pin "P$10") (pinfunction "SH_P$10") (pintype "passive"))
      (node (ref "SD100") (pin "P$11") (pinfunction "SH_P$11") (pintype "passive"))
      (node (ref "SD100") (pin "P$12") (pinfunction "SH_P$12") (pintype "passive"))
      (node (ref "SD100") (pin "P$13") (pinfunction "SH_P$13") (pintype "passive"))
      (node (ref "SD100") (pin "P$4") (pinfunction "VSS_P$4") (pintype "power_in"))
      (node (ref "TILE1") (pin "0V@1") (pinfunction "0V_0V@1") (pintype "power_in"))
      (node (ref "TILE1") (pin "0V@2") (pinfunction "0V_0V@2") (pintype "power_in"))
      (node (ref "TILE1") (pin "P$1") (pinfunction "V-_P$1") (pintype "power_in"))
      (node (ref "TILE1") (pin "P$2") (pinfunction "V-_P$2") (pintype "power_in"))
      (node (ref "TILE1") (pin "P$26") (pinfunction "V-_P$26") (pintype "power_in"))
      (node (ref "TILE1") (pin "P$27") (pinfunction "V-_P$27") (pintype "power_in"))
      (node (ref "TILE1") (pin "P$28") (pinfunction "V-_P$28") (pintype "power_in"))
      (node (ref "TILE1") (pin "P$29") (pinfunction "V-_P$29") (pintype "power_in"))
      (node (ref "TILE1") (pin "P$3") (pinfunction "V-_P$3") (pintype "power_in"))
      (node (ref "TILE1") (pin "P$30") (pinfunction "V-_P$30") (pintype "power_in"))
      (node (ref "TILE1") (pin "P$31") (pinfunction "V-_P$31") (pintype "power_in"))
      (node (ref "TILE1") (pin "P$32") (pinfunction "GND_P$32") (pintype "power_in"))
      (node (ref "TILE1") (pin "P$4") (pinfunction "V-_P$4") (pintype "power_in"))
      (node (ref "TILE1") (pin "P$5") (pinfunction "V-_P$5") (pintype "power_in"))
      (node (ref "TILE1") (pin "P$6") (pinfunction "V-_P$6") (pintype "power_in"))
      (node (ref "TILE1") (pin "P$7") (pinfunction "GND_P$7") (pintype "power_in"))
      (node (ref "TILE2") (pin "0V@1") (pinfunction "0V_0V@1") (pintype "power_in"))
      (node (ref "TILE2") (pin "0V@2") (pinfunction "0V_0V@2") (pintype "power_in"))
      (node (ref "TILE2") (pin "P$1") (pinfunction "V-_P$1") (pintype "power_in"))
      (node (ref "TILE2") (pin "P$2") (pinfunction "V-_P$2") (pintype "power_in"))
      (node (ref "TILE2") (pin "P$26") (pinfunction "V-_P$26") (pintype "power_in"))
      (node (ref "TILE2") (pin "P$27") (pinfunction "V-_P$27") (pintype "power_in"))
      (node (ref "TILE2") (pin "P$28") (pinfunction "V-_P$28") (pintype "power_in"))
      (node (ref "TILE2") (pin "P$29") (pinfunction "V-_P$29") (pintype "power_in"))
      (node (ref "TILE2") (pin "P$3") (pinfunction "V-_P$3") (pintype "power_in"))
      (node (ref "TILE2") (pin "P$30") (pinfunction "V-_P$30") (pintype "power_in"))
      (node (ref "TILE2") (pin "P$31") (pinfunction "V-_P$31") (pintype "power_in"))
      (node (ref "TILE2") (pin "P$32") (pinfunction "GND_P$32") (pintype "power_in"))
      (node (ref "TILE2") (pin "P$4") (pinfunction "V-_P$4") (pintype "power_in"))
      (node (ref "TILE2") (pin "P$5") (pinfunction "V-_P$5") (pintype "power_in"))
      (node (ref "TILE2") (pin "P$6") (pinfunction "V-_P$6") (pintype "power_in"))
      (node (ref "TILE2") (pin "P$7") (pinfunction "GND_P$7") (pintype "power_in"))
      (node (ref "TILE3") (pin "0V@1") (pinfunction "0V_0V@1") (pintype "power_in"))
      (node (ref "TILE3") (pin "0V@2") (pinfunction "0V_0V@2") (pintype "power_in"))
      (node (ref "TILE3") (pin "P$1") (pinfunction "V-_P$1") (pintype "power_in"))
      (node (ref "TILE3") (pin "P$2") (pinfunction "V-_P$2") (pintype "power_in"))
      (node (ref "TILE3") (pin "P$26") (pinfunction "V-_P$26") (pintype "power_in"))
      (node (ref "TILE3") (pin "P$27") (pinfunction "V-_P$27") (pintype "power_in"))
      (node (ref "TILE3") (pin "P$28") (pinfunction "V-_P$28") (pintype "power_in"))
      (node (ref "TILE3") (pin "P$29") (pinfunction "V-_P$29") (pintype "power_in"))
      (node (ref "TILE3") (pin "P$3") (pinfunction "V-_P$3") (pintype "power_in"))
      (node (ref "TILE3") (pin "P$30") (pinfunction "V-_P$30") (pintype "power_in"))
      (node (ref "TILE3") (pin "P$31") (pinfunction "V-_P$31") (pintype "power_in"))
      (node (ref "TILE3") (pin "P$32") (pinfunction "GND_P$32") (pintype "power_in"))
      (node (ref "TILE3") (pin "P$4") (pinfunction "V-_P$4") (pintype "power_in"))
      (node (ref "TILE3") (pin "P$5") (pinfunction "V-_P$5") (pintype "power_in"))
      (node (ref "TILE3") (pin "P$6") (pinfunction "V-_P$6") (pintype "power_in"))
      (node (ref "TILE3") (pin "P$7") (pinfunction "GND_P$7") (pintype "power_in"))
      (node (ref "TILE4") (pin "0V@1") (pinfunction "0V_0V@1") (pintype "power_in"))
      (node (ref "TILE4") (pin "0V@2") (pinfunction "0V_0V@2") (pintype "power_in"))
      (node (ref "TILE4") (pin "P$1") (pinfunction "V-_P$1") (pintype "power_in"))
      (node (ref "TILE4") (pin "P$2") (pinfunction "V-_P$2") (pintype "power_in"))
      (node (ref "TILE4") (pin "P$26") (pinfunction "V-_P$26") (pintype "power_in"))
      (node (ref "TILE4") (pin "P$27") (pinfunction "V-_P$27") (pintype "power_in"))
      (node (ref "TILE4") (pin "P$28") (pinfunction "V-_P$28") (pintype "power_in"))
      (node (ref "TILE4") (pin "P$29") (pinfunction "V-_P$29") (pintype "power_in"))
      (node (ref "TILE4") (pin "P$3") (pinfunction "V-_P$3") (pintype "power_in"))
      (node (ref "TILE4") (pin "P$30") (pinfunction "V-_P$30") (pintype "power_in"))
      (node (ref "TILE4") (pin "P$31") (pinfunction "V-_P$31") (pintype "power_in"))
      (node (ref "TILE4") (pin "P$32") (pinfunction "GND_P$32") (pintype "power_in"))
      (node (ref "TILE4") (pin "P$4") (pinfunction "V-_P$4") (pintype "power_in"))
      (node (ref "TILE4") (pin "P$5") (pinfunction "V-_P$5") (pintype "power_in"))
      (node (ref "TILE4") (pin "P$6") (pinfunction "V-_P$6") (pintype "power_in"))
      (node (ref "TILE4") (pin "P$7") (pinfunction "GND_P$7") (pintype "power_in"))
      (node (ref "TILE5") (pin "0V@1") (pinfunction "0V_0V@1") (pintype "power_in"))
      (node (ref "TILE5") (pin "0V@2") (pinfunction "0V_0V@2") (pintype "power_in"))
      (node (ref "TILE5") (pin "P$1") (pinfunction "V-_P$1") (pintype "power_in"))
      (node (ref "TILE5") (pin "P$2") (pinfunction "V-_P$2") (pintype "power_in"))
      (node (ref "TILE5") (pin "P$26") (pinfunction "V-_P$26") (pintype "power_in"))
      (node (ref "TILE5") (pin "P$27") (pinfunction "V-_P$27") (pintype "power_in"))
      (node (ref "TILE5") (pin "P$28") (pinfunction "V-_P$28") (pintype "power_in"))
      (node (ref "TILE5") (pin "P$29") (pinfunction "V-_P$29") (pintype "power_in"))
      (node (ref "TILE5") (pin "P$3") (pinfunction "V-_P$3") (pintype "power_in"))
      (node (ref "TILE5") (pin "P$30") (pinfunction "V-_P$30") (pintype "power_in"))
      (node (ref "TILE5") (pin "P$31") (pinfunction "V-_P$31") (pintype "power_in"))
      (node (ref "TILE5") (pin "P$32") (pinfunction "GND_P$32") (pintype "power_in"))
      (node (ref "TILE5") (pin "P$4") (pinfunction "V-_P$4") (pintype "power_in"))
      (node (ref "TILE5") (pin "P$5") (pinfunction "V-_P$5") (pintype "power_in"))
      (node (ref "TILE5") (pin "P$6") (pinfunction "V-_P$6") (pintype "power_in"))
      (node (ref "TILE5") (pin "P$7") (pinfunction "GND_P$7") (pintype "power_in"))
      (node (ref "TILE6") (pin "E13") (pinfunction "E13_E13") (pintype "bidirectional"))
      (node (ref "TILE6") (pin "E14") (pinfunction "E14_E14") (pintype "bidirectional"))
      (node (ref "TILE6") (pin "F10") (pinfunction "F10_F10") (pintype "bidirectional"))
      (node (ref "TILE6") (pin "F11") (pinfunction "F11_F11") (pintype "bidirectional"))
      (node (ref "TILE6") (pin "F12") (pinfunction "F12_F12") (pintype "bidirectional"))
      (node (ref "TILE6") (pin "F19") (pinfunction "F19_F19") (pintype "bidirectional"))
      (node (ref "TILE6") (pin "F7") (pinfunction "F7_F7") (pintype "bidirectional"))
      (node (ref "TILE6") (pin "F8") (pinfunction "F8_F8") (pintype "bidirectional"))
      (node (ref "TILE6") (pin "F9") (pinfunction "F9_F9") (pintype "bidirectional"))
      (node (ref "Y1") (pin "2") (pinfunction "GND_2") (pintype "power_in"))
      (node (ref "Y1") (pin "4") (pinfunction "GND_4") (pintype "passive"))
    )
    (net (code "199") (name "Net-(IC1-FB)") (class "Default")
      (node (ref "C5") (pin "1") (pinfunction "1_1") (pintype "passive"))
      (node (ref "IC1") (pin "5") (pinfunction "FB_5") (pintype "input"))
      (node (ref "R1") (pin "1") (pinfunction "1_1") (pintype "passive"))
      (node (ref "R2") (pin "1") (pinfunction "1_1") (pintype "passive"))
    )
    (net (code "200") (name "Net-(IC1-LX)") (class "Default")
      (node (ref "I1") (pin "P$1") (pinfunction "P$1_P$1") (pintype "passive"))
      (node (ref "IC1") (pin "3") (pinfunction "LX_3") (pintype "power_in"))
    )
    (net (code "201") (name "Net-(IC5-FB)") (class "Default")
      (node (ref "C11") (pin "1") (pinfunction "1_1") (pintype "passive"))
      (node (ref "IC5") (pin "5") (pinfunction "FB_5") (pintype "input"))
      (node (ref "R5") (pin "1") (pinfunction "1_1") (pintype "passive"))
      (node (ref "R6") (pin "1") (pinfunction "1_1") (pintype "passive"))
    )
    (net (code "202") (name "Net-(IC5-LX)") (class "Default")
      (node (ref "I2") (pin "P$1") (pinfunction "P$1_P$1") (pintype "passive"))
      (node (ref "IC5") (pin "3") (pinfunction "LX_3") (pintype "power_in"))
    )
    (net (code "203") (name "Net-(IC9-PC14-OSC32_IN)") (class "Default")
      (node (ref "C28") (pin "2") (pinfunction "2_2") (pintype "passive"))
      (node (ref "IC9") (pin "8") (pinfunction "PC14-OSC32_IN_8") (pintype "bidirectional"))
      (node (ref "Y2") (pin "P$2") (pinfunction "X2_P$2") (pintype "passive"))
    )
    (net (code "204") (name "Net-(IC9-PC15-OSC32_OUT)") (class "Default")
      (node (ref "C26") (pin "2") (pinfunction "2_2") (pintype "passive"))
      (node (ref "IC9") (pin "9") (pinfunction "PC15-OSC32_OUT_9") (pintype "bidirectional"))
      (node (ref "Y2") (pin "P$1") (pinfunction "X1_P$1") (pintype "passive"))
    )
    (net (code "205") (name "Net-(IC9-PH0-OSC_IN)") (class "Default")
      (node (ref "C27") (pin "2") (pinfunction "2_2") (pintype "passive"))
      (node (ref "IC9") (pin "12") (pinfunction "PH0-OSC_IN_12") (pintype "bidirectional"))
      (node (ref "Y1") (pin "1") (pinfunction "X1_1") (pintype "passive"))
    )
    (net (code "206") (name "Net-(IC9-PH1-OSC_OUT)") (class "Default")
      (node (ref "C29") (pin "2") (pinfunction "2_2") (pintype "passive"))
      (node (ref "IC9") (pin "13") (pinfunction "PH1-OSC_OUT_13") (pintype "bidirectional"))
      (node (ref "Y1") (pin "3") (pinfunction "X2_3") (pintype "passive"))
    )
    (net (code "207") (name "Net-(IC9-VCAP1)") (class "Default")
      (node (ref "C18") (pin "2") (pinfunction "2_2") (pintype "passive"))
      (node (ref "IC9") (pin "48") (pinfunction "VCAP1_48") (pintype "bidirectional"))
    )
    (net (code "208") (name "Net-(IC9-VCAP2)") (class "Default")
      (node (ref "C15") (pin "1") (pinfunction "1_1") (pintype "passive"))
      (node (ref "IC9") (pin "73") (pinfunction "VCAP2_73") (pintype "bidirectional"))
    )
    (net (code "209") (name "Net-(IC9-VDDA)") (class "Default")
      (node (ref "C25") (pin "1") (pinfunction "1_1") (pintype "passive"))
      (node (ref "IC9") (pin "20") (pinfunction "VREF+_20") (pintype "bidirectional"))
      (node (ref "IC9") (pin "21") (pinfunction "VDDA_21") (pintype "bidirectional"))
      (node (ref "R7") (pin "1") (pinfunction "1_1") (pintype "passive"))
    )
    (net (code "210") (name "Net-(L1-BC)") (class "Default")
      (node (ref "L1") (pin "B") (pinfunction "BC_B") (pintype "bidirectional"))
      (node (ref "RN8") (pin "3") (pinfunction "1_3") (pintype "passive"))
    )
    (net (code "211") (name "Net-(L1-GC)") (class "Default")
      (node (ref "L1") (pin "G") (pinfunction "GC_G") (pintype "bidirectional"))
      (node (ref "RN8") (pin "2") (pinfunction "1_2") (pintype "passive"))
    )
    (net (code "212") (name "Net-(L1-RC)") (class "Default")
      (node (ref "L1") (pin "R") (pinfunction "RC_R") (pintype "bidirectional"))
      (node (ref "RN8") (pin "1") (pinfunction "1_1") (pintype "passive"))
    )
    (net (code "213") (name "Net-(L2-PadA)") (class "Default")
      (node (ref "L2") (pin "A") (pinfunction "A_A") (pintype "passive"))
      (node (ref "R9") (pin "2") (pinfunction "2_2") (pintype "passive"))
    )
    (net (code "214") (name "unconnected-(CN1-PadSBU1)") (class "Default")
      (node (ref "CN1") (pin "SBU1") (pinfunction "SBU1_SBU1") (pintype "bidirectional"))
    )
    (net (code "215") (name "unconnected-(CN1-PadSBU2)") (class "Default")
      (node (ref "CN1") (pin "SBU2") (pinfunction "SBU2_SBU2") (pintype "bidirectional"))
    )
    (net (code "216") (name "unconnected-(CN2-PadSBU1)") (class "Default")
      (node (ref "CN2") (pin "SBU1") (pinfunction "SBU1_SBU1") (pintype "bidirectional"))
    )
    (net (code "217") (name "unconnected-(CN2-PadSBU2)") (class "Default")
      (node (ref "CN2") (pin "SBU2") (pinfunction "SBU2_SBU2") (pintype "bidirectional"))
    )
    (net (code "218") (name "unconnected-(CN3-Pad4)") (class "Default")
      (node (ref "CN3") (pin "4") (pinfunction "4_4") (pintype "bidirectional"))
    )
    (net (code "219") (name "unconnected-(CN3-Pad7)") (class "Default")
      (node (ref "CN3") (pin "7") (pinfunction "7_7") (pintype "bidirectional"))
    )
    (net (code "220") (name "unconnected-(IC2-NC-Pad4)") (class "Default")
      (node (ref "IC2") (pin "4") (pinfunction "NC_4") (pintype "no_connect"))
    )
    (net (code "221") (name "unconnected-(IC3-VPP_FAST-PadB10)") (class "Default")
      (node (ref "IC3") (pin "B10") (pinfunction "VPP_FAST_B10") (pintype "bidirectional"))
    )
    (net (code "222") (name "unconnected-(IC6-CK#-PadB1)") (class "Default")
      (node (ref "IC6") (pin "B1") (pinfunction "CK#_B1") (pintype "bidirectional"))
    )
    (net (code "223") (name "unconnected-(IC6-RFU_1-PadA2)") (class "Default")
      (node (ref "IC6") (pin "A2") (pinfunction "RFU_1_A2") (pintype "bidirectional"))
    )
    (net (code "224") (name "unconnected-(IC6-RFU_2-PadA5)") (class "Default")
      (node (ref "IC6") (pin "A5") (pinfunction "RFU_2_A5") (pintype "bidirectional"))
    )
    (net (code "225") (name "unconnected-(IC6-RFU_3-PadB5)") (class "Default")
      (node (ref "IC6") (pin "B5") (pinfunction "RFU_3_B5") (pintype "bidirectional"))
    )
    (net (code "226") (name "unconnected-(IC6-RFU_4-PadC2)") (class "Default")
      (node (ref "IC6") (pin "C2") (pinfunction "RFU_4_C2") (pintype "bidirectional"))
    )
    (net (code "227") (name "unconnected-(IC6-RFU_5-PadC5)") (class "Default")
      (node (ref "IC6") (pin "C5") (pinfunction "RFU_5_C5") (pintype "bidirectional"))
    )
    (net (code "228") (name "unconnected-(IC6-VCC-PadB4)") (class "Default")
      (node (ref "IC6") (pin "B4") (pinfunction "VCC_B4") (pintype "bidirectional"))
    )
    (net (code "229") (name "unconnected-(IC7-I{slash}O1_2-Pad6)") (class "Default")
      (node (ref "IC7") (pin "6") (pinfunction "I/O1_2_6") (pintype "bidirectional"))
    )
    (net (code "230") (name "unconnected-(IC7-I{slash}O2_2-Pad4)") (class "Default")
      (node (ref "IC7") (pin "4") (pinfunction "I/O2_2_4") (pintype "bidirectional"))
    )
    (net (code "231") (name "unconnected-(IC8-I{slash}O1_1-Pad1)") (class "Default")
      (node (ref "IC8") (pin "1") (pinfunction "I/O1_1_1") (pintype "bidirectional"))
    )
    (net (code "232") (name "unconnected-(IC8-I{slash}O2_1-Pad3)") (class "Default")
      (node (ref "IC8") (pin "3") (pinfunction "I/O2_1_3") (pintype "bidirectional"))
    )
    (net (code "233") (name "unconnected-(IC9-VDD_1-Pad11)") (class "Default")
      (node (ref "IC9") (pin "11") (pinfunction "VDD_1_11") (pintype "bidirectional"))
    )
    (net (code "234") (name "unconnected-(IC9-VSS_1-Pad10)") (class "Default")
      (node (ref "IC9") (pin "10") (pinfunction "VSS_1_10") (pintype "bidirectional"))
    )
    (net (code "235") (name "unconnected-(IC9-VSS_5-Pad99)") (class "Default")
      (node (ref "IC9") (pin "99") (pinfunction "VSS_5_99") (pintype "bidirectional"))
    )
    (net (code "236") (name "unconnected-(IC10-N{slash}C-Pad15)") (class "Default")
      (node (ref "IC10") (pin "15") (pinfunction "N/C_15") (pintype "no_connect"))
    )
    (net (code "237") (name "unconnected-(RN6C-1-Pad3)") (class "Default")
      (node (ref "RN6") (pin "3") (pinfunction "1_3") (pintype "passive"))
    )
    (net (code "238") (name "unconnected-(RN6C-2-Pad6)") (class "Default")
      (node (ref "RN6") (pin "6") (pinfunction "2_6") (pintype "passive"))
    )
    (net (code "239") (name "unconnected-(RN6D-1-Pad4)") (class "Default")
      (node (ref "RN6") (pin "4") (pinfunction "1_4") (pintype "passive"))
    )
    (net (code "240") (name "unconnected-(RN6D-2-Pad5)") (class "Default")
      (node (ref "RN6") (pin "5") (pinfunction "2_5") (pintype "passive"))
    )
    (net (code "241") (name "unconnected-(RN9C-1-Pad3)") (class "Default")
      (node (ref "RN9") (pin "3") (pinfunction "1_3") (pintype "passive"))
    )
    (net (code "242") (name "unconnected-(RN9C-2-Pad6)") (class "Default")
      (node (ref "RN9") (pin "6") (pinfunction "2_6") (pintype "passive"))
    )
    (net (code "243") (name "unconnected-(RN9D-1-Pad4)") (class "Default")
      (node (ref "RN9") (pin "4") (pinfunction "1_4") (pintype "passive"))
    )
    (net (code "244") (name "unconnected-(RN9D-2-Pad5)") (class "Default")
      (node (ref "RN9") (pin "5") (pinfunction "2_5") (pintype "passive"))
    )
    (net (code "245") (name "unconnected-(TILE6-PadF6)") (class "Default")
      (node (ref "TILE6") (pin "F6") (pinfunction "F6_F6") (pintype "bidirectional"))
    )
  )
)
